# DS_ZK_FINAL.net
KiCad netlist of a schematic drawn in Altium Designer
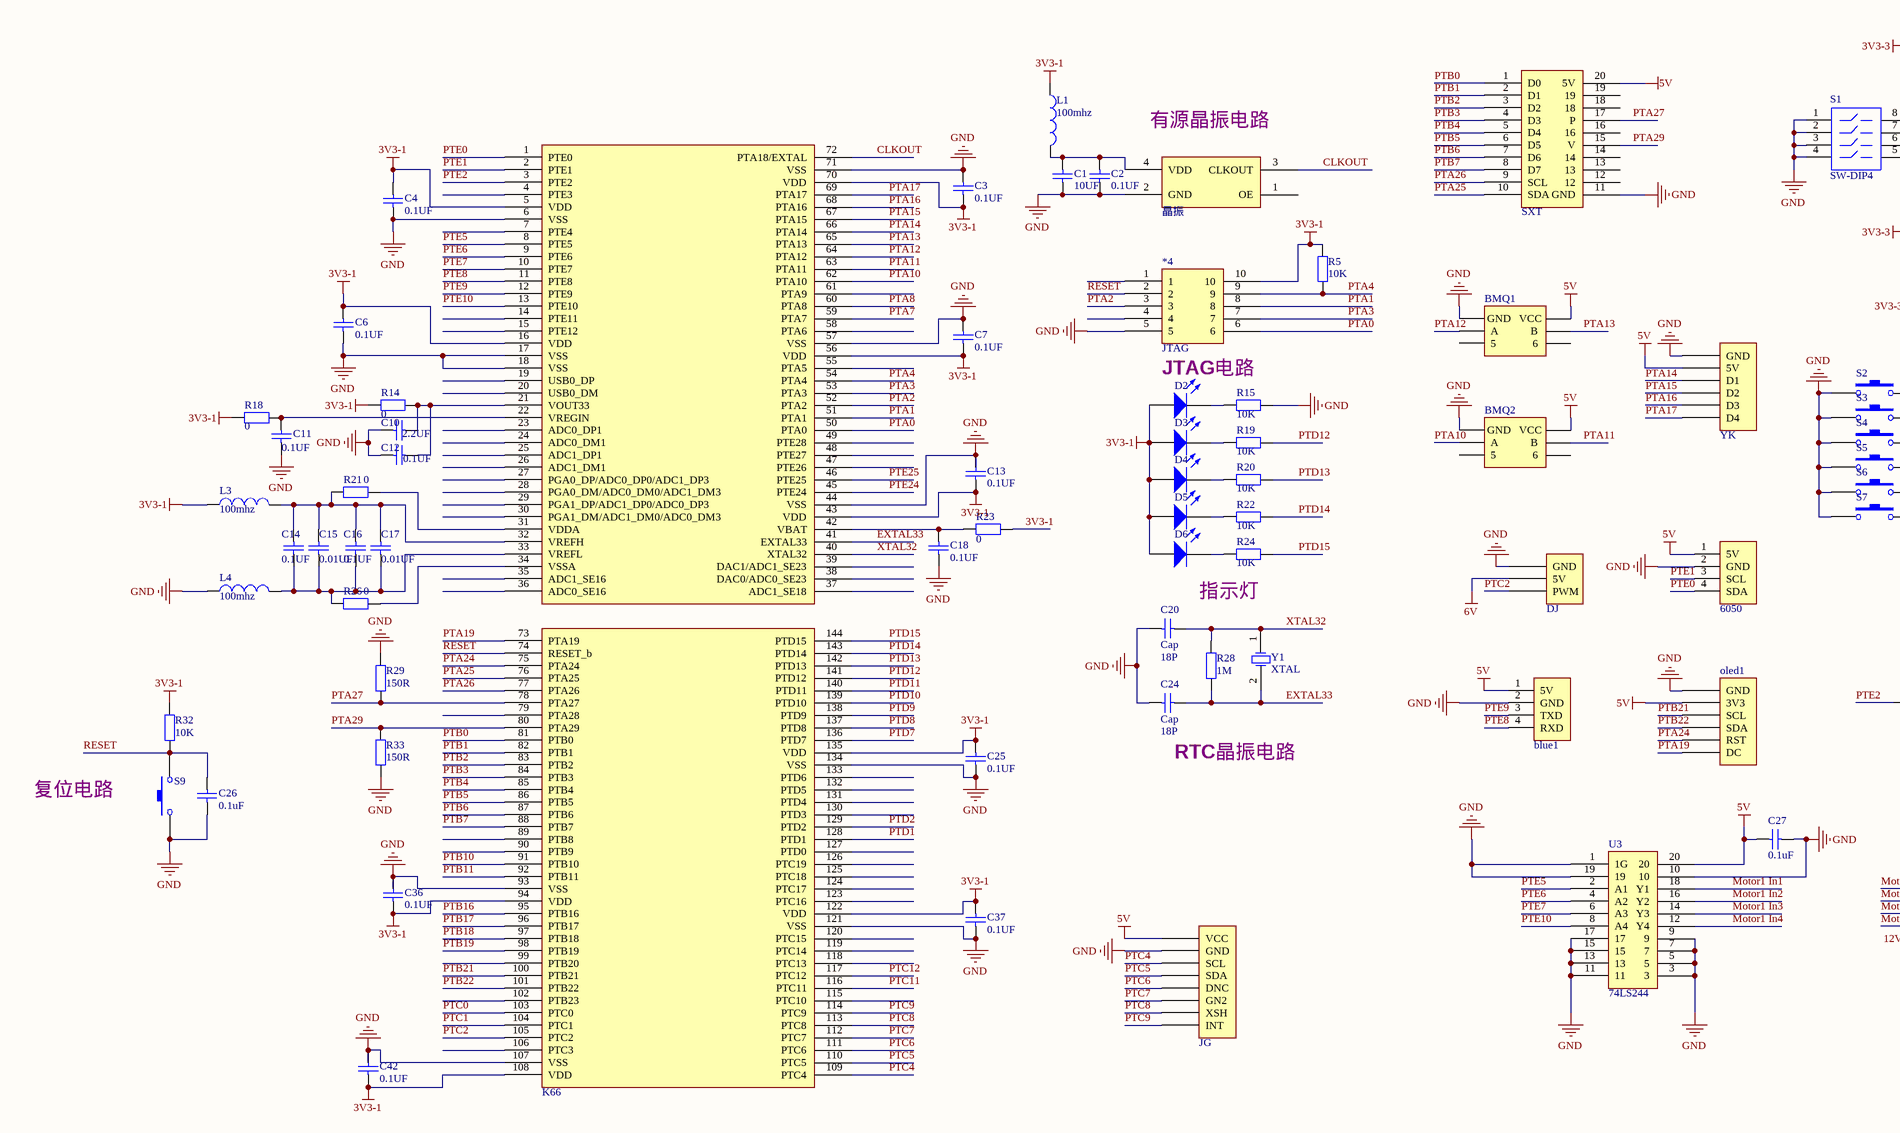
[diagram p0: DS_ZK_FINAL.SchDoc, top left]
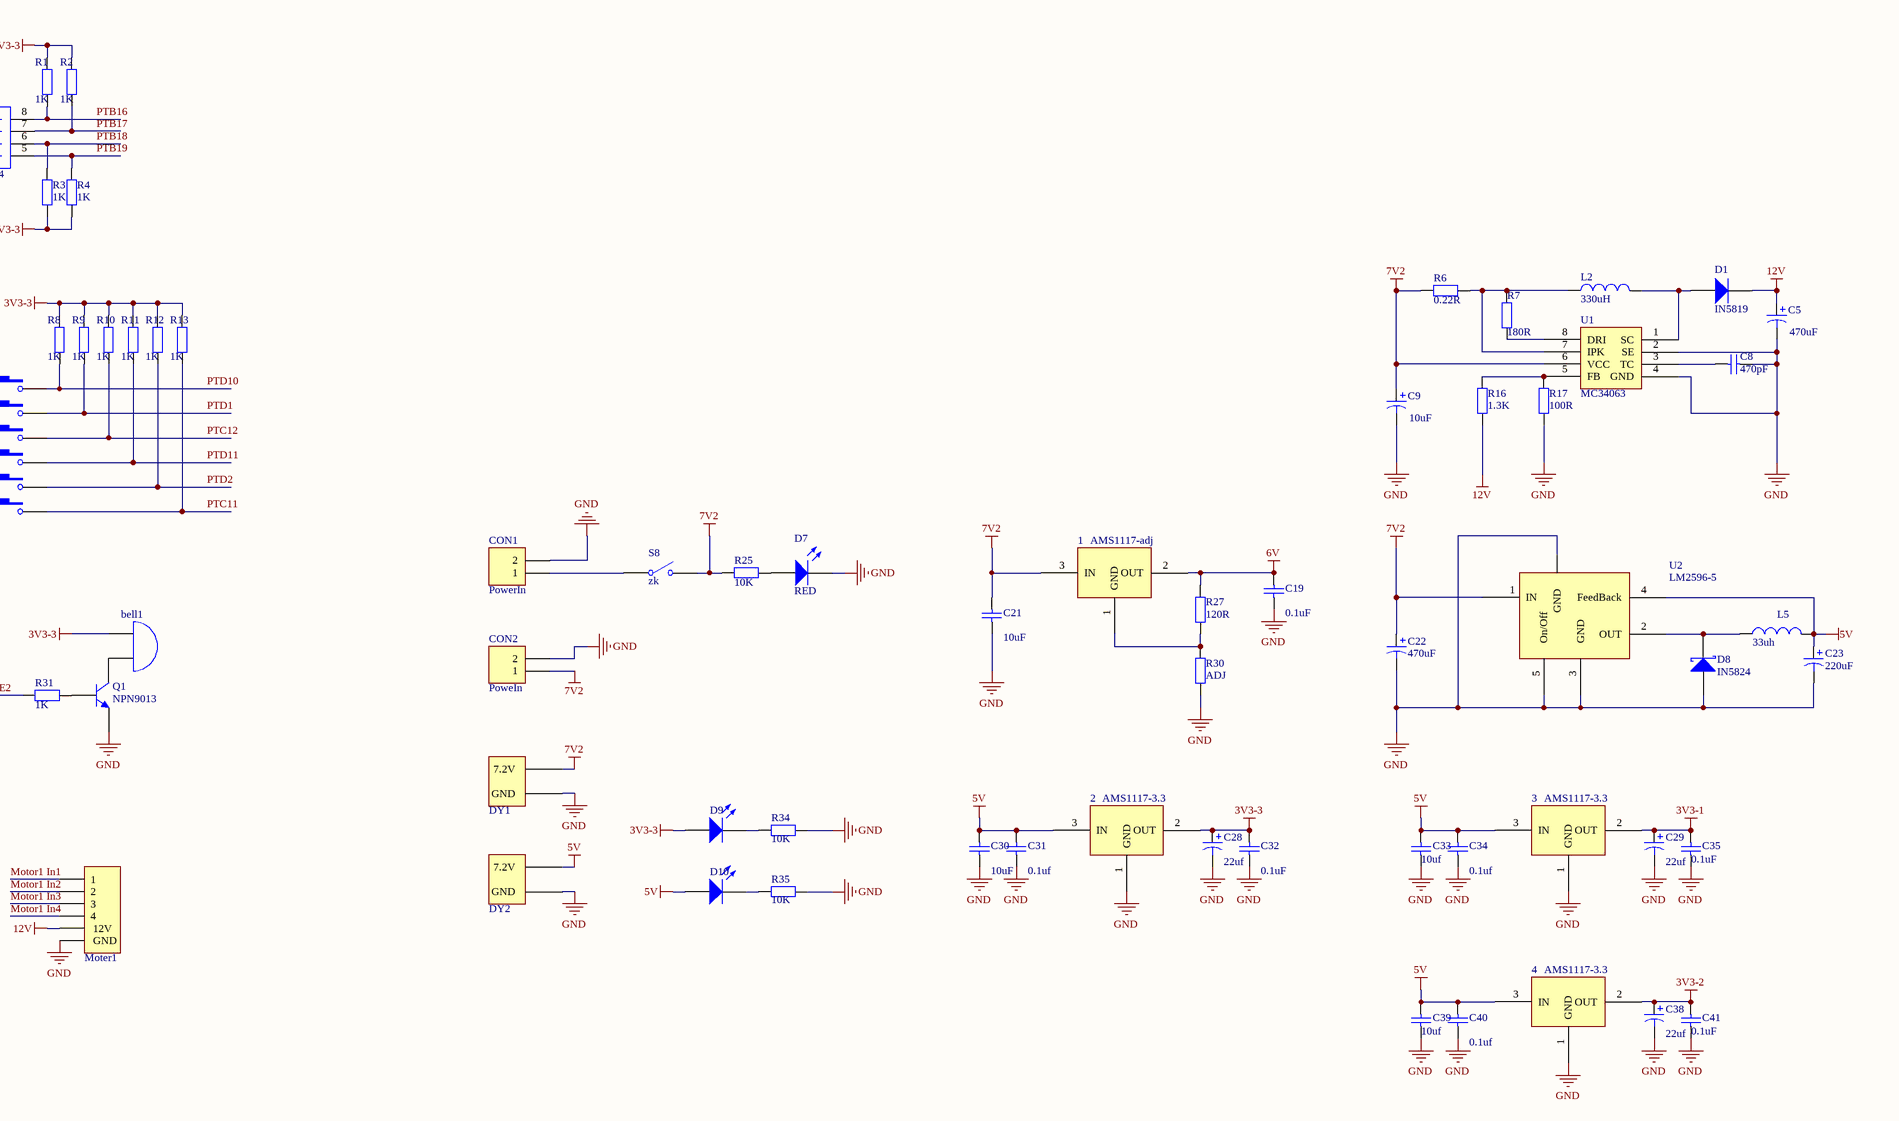
[diagram p1: DS_ZK_FINAL.SchDoc, top right]
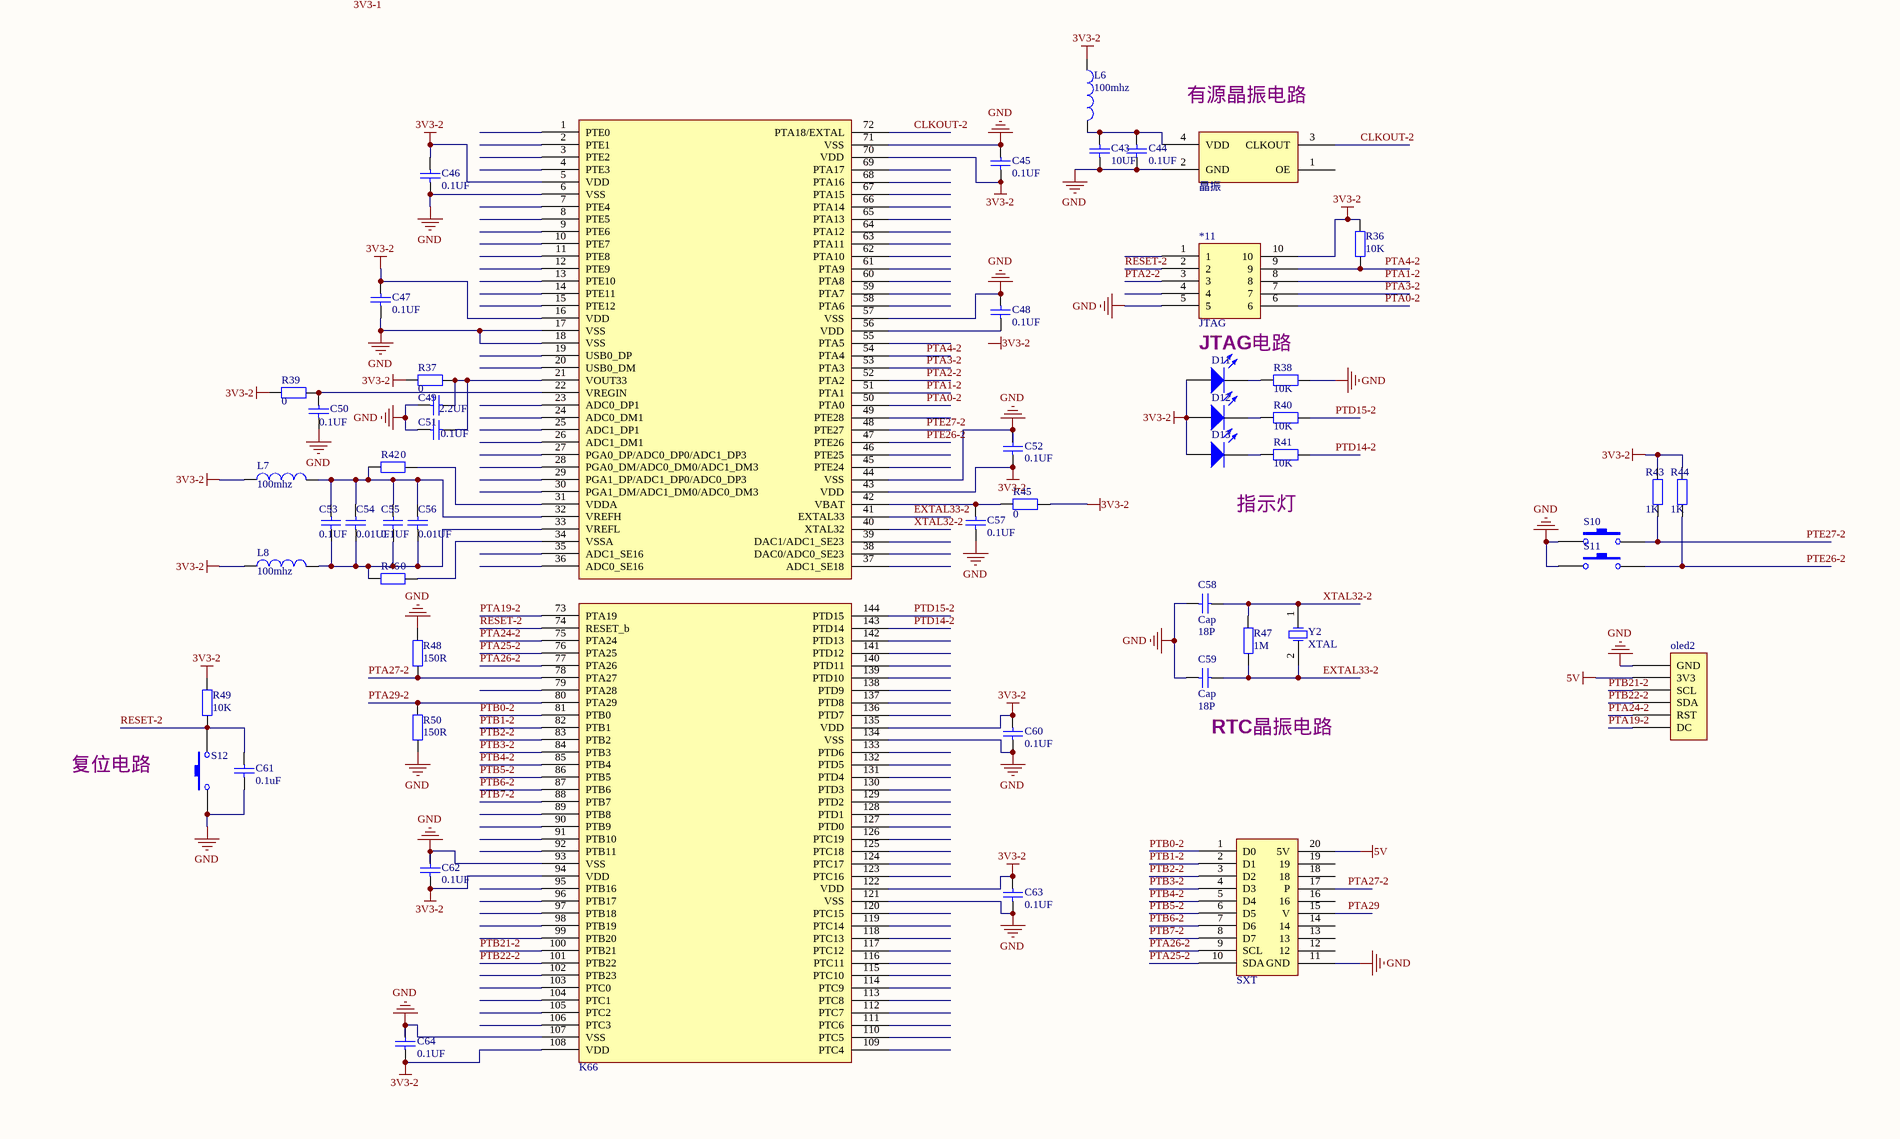
[diagram p2: DS_ZK_FINAL.SchDoc, bottom left]

(export (version "E")
  (design (tool "Eeschema 10.0.6"))
  (components
    (comp (ref "*1") (value "SXT") (footprint "SXT") (libsource (lib "DS_zk") (part "摄像头")))
    (comp (ref "*2") (value "K66") (footprint "LC-LQFP-144_20x20x05P") (libsource (lib "DS_zk") (part "K66")))
    (comp (ref "*3") (value "晶振") (footprint "LC-SMD-7050_4P") (libsource (lib "DS_zk") (part "晶振")))
    (comp (ref "*4") (value "JTAG") (footprint "HDR2X5") (libsource (lib "DS_zk") (part "JTAG")))
    (comp (ref "*5") (value "YK") (footprint "HDR1X6") (libsource (lib "DS_zk") (part "遥控")))
    (comp (ref "*6") (value "6050") (footprint "HDR1X4") (libsource (lib "DS_zk") (part "6050")))
    (comp (ref "*7") (value "DJ") (footprint "HDR1X3") (libsource (lib "DS_zk") (part "舵机")))
    (comp (ref "*8") (value "JG") (footprint "HDR1X8") (libsource (lib "DS_zk") (part "激光")))
    (comp (ref "*9") (value "K66") (footprint "LC-LQFP-144_20x20x05P") (libsource (lib "DS_zk") (part "K66")))
    (comp (ref "*10") (value "晶振") (footprint "LC-SMD-7050_4P") (libsource (lib "DS_zk") (part "晶振")))
    (comp (ref "*11") (value "JTAG") (footprint "HDR2X5") (libsource (lib "DS_zk") (part "JTAG")))
    (comp (ref "*12") (value "SXT") (footprint "SXT") (libsource (lib "DS_zk") (part "摄像头")))
    (comp (ref "1")
      (value "AMS1117-adj")
      (footprint "lm1117-5v")
      (libsource (lib "红牛板Schlib") (part "LT1117-3.3"))
    )
    (comp (ref "2")
      (value "AMS1117-3.3")
      (footprint "lm1117-5v")
      (libsource (lib "红牛板Schlib") (part "LT1117-3.3"))
    )
    (comp (ref "3")
      (value "AMS1117-3.3")
      (footprint "lm1117-5v")
      (libsource (lib "红牛板Schlib") (part "LT1117-3.3"))
    )
    (comp (ref "4")
      (value "AMS1117-3.3")
      (footprint "lm1117-5v")
      (libsource (lib "红牛板Schlib") (part "LT1117-3.3"))
    )
    (comp (ref "bell1")
      (value "Bell")
      (footprint "bezzer")
      (description "Electrical Bell")
      (fields (field (name "PUBLISHER") "Altium Limited"))
      (libsource (lib "Miscellaneous Devices") (part "Bell"))
    )
    (comp (ref "blue1")
      (value "blueteeth2")
      (footprint "HDR1X4")
      (libsource (lib "DS_zk") (part "blueteeth"))
    )
    (comp (ref "BMQ1") (value "encode_1") (footprint "HDR2X3") (libsource (lib "主控板原理图") (part "encode")))
    (comp (ref "BMQ2") (value "encode_2") (footprint "HDR2X3") (libsource (lib "主控板原理图") (part "encode")))
    (comp (ref "C1")
      (value "10UF")
      (footprint "0603")
      (description "Capacitor")
      (fields (field (name "Comment") "Cap") (field (name "PUBLISHER") "Altium Limited"))
      (libsource (lib "Miscellaneous Devices") (part "Cap"))
    )
    (comp (ref "C2")
      (value "0.1UF")
      (footprint "0603")
      (description "Capacitor")
      (fields (field (name "Comment") "Cap") (field (name "PUBLISHER") "Altium Limited"))
      (libsource (lib "Miscellaneous Devices") (part "Cap"))
    )
    (comp (ref "C3")
      (value "0.1UF")
      (footprint "0603")
      (description "Capacitor")
      (fields (field (name "Comment") "Cap") (field (name "PUBLISHER") "Altium Limited"))
      (libsource (lib "Miscellaneous Devices") (part "Cap"))
    )
    (comp (ref "C4")
      (value "0.1UF")
      (footprint "0603")
      (description "Capacitor")
      (fields (field (name "Comment") "Cap") (field (name "PUBLISHER") "Altium Limited"))
      (libsource (lib "Miscellaneous Devices") (part "Cap"))
    )
    (comp (ref "C5")
      (value "470uF")
      (footprint "470UF")
      (description "Polarized Capacitor (Surface Mount)")
      (fields (field (name "PUBLISHER") "Altium Limited"))
      (libsource (lib "Miscellaneous Devices") (part "Cap Pol3"))
    )
    (comp (ref "C6")
      (value "0.1UF")
      (footprint "0603")
      (description "Capacitor")
      (fields (field (name "Comment") "Cap") (field (name "PUBLISHER") "Altium Limited"))
      (libsource (lib "Miscellaneous Devices") (part "Cap"))
    )
    (comp (ref "C7")
      (value "0.1UF")
      (footprint "0603")
      (description "Capacitor")
      (fields (field (name "Comment") "Cap") (field (name "PUBLISHER") "Altium Limited"))
      (libsource (lib "Miscellaneous Devices") (part "Cap"))
    )
    (comp (ref "C8")
      (value "470pF")
      (footprint "0805")
      (description "Capacitor (Semiconductor SIM Model)")
      (fields (field (name "PUBLISHER") "Altium Limited"))
      (libsource (lib "Miscellaneous Devices") (part "Cap Semi"))
    )
    (comp (ref "C9")
      (value "10uF")
      (footprint "0805")
      (description "Polarized Capacitor (Surface Mount)")
      (fields (field (name "PUBLISHER") "Altium Limited"))
      (libsource (lib "Miscellaneous Devices") (part "Cap Pol3"))
    )
    (comp (ref "C10")
      (value "2.2UF")
      (footprint "0603")
      (description "Capacitor")
      (fields (field (name "Comment") "Cap") (field (name "PUBLISHER") "Altium Limited"))
      (libsource (lib "Miscellaneous Devices") (part "Cap"))
    )
    (comp (ref "C11")
      (value "0.1UF")
      (footprint "0603")
      (description "Capacitor")
      (fields (field (name "Comment") "Cap") (field (name "PUBLISHER") "Altium Limited"))
      (libsource (lib "Miscellaneous Devices") (part "Cap"))
    )
    (comp (ref "C12")
      (value "0.1UF")
      (footprint "0603")
      (description "Capacitor")
      (fields (field (name "Comment") "Cap") (field (name "PUBLISHER") "Altium Limited"))
      (libsource (lib "Miscellaneous Devices") (part "Cap"))
    )
    (comp (ref "C13")
      (value "0.1UF")
      (footprint "0603")
      (description "Capacitor")
      (fields (field (name "Comment") "Cap") (field (name "PUBLISHER") "Altium Limited"))
      (libsource (lib "Miscellaneous Devices") (part "Cap"))
    )
    (comp (ref "C14")
      (value "0.1UF")
      (footprint "0603")
      (description "Capacitor")
      (fields (field (name "Comment") "Cap") (field (name "PUBLISHER") "Altium Limited"))
      (libsource (lib "Miscellaneous Devices") (part "Cap"))
    )
    (comp (ref "C15")
      (value "0.01UF")
      (footprint "0603")
      (description "Capacitor")
      (fields (field (name "Comment") "Cap") (field (name "PUBLISHER") "Altium Limited"))
      (libsource (lib "Miscellaneous Devices") (part "Cap"))
    )
    (comp (ref "C16")
      (value "0.1UF")
      (footprint "0603")
      (description "Capacitor")
      (fields (field (name "Comment") "Cap") (field (name "PUBLISHER") "Altium Limited"))
      (libsource (lib "Miscellaneous Devices") (part "Cap"))
    )
    (comp (ref "C17")
      (value "0.01UF")
      (footprint "0603")
      (description "Capacitor")
      (fields (field (name "Comment") "Cap") (field (name "PUBLISHER") "Altium Limited"))
      (libsource (lib "Miscellaneous Devices") (part "Cap"))
    )
    (comp (ref "C18")
      (value "0.1UF")
      (footprint "0603")
      (description "Capacitor")
      (fields (field (name "Comment") "Cap") (field (name "PUBLISHER") "Altium Limited"))
      (libsource (lib "Miscellaneous Devices") (part "Cap"))
    )
    (comp (ref "C19")
      (value "0.1uF")
      (footprint "0805")
      (description "Capacitor")
      (fields (field (name "Comment") "Cap") (field (name "PUBLISHER") "Altium Limited"))
      (libsource (lib "Miscellaneous Devices") (part "Cap"))
    )
    (comp (ref "C20")
      (value "Cap")
      (footprint "0603")
      (description "Capacitor")
      (fields (field (name "ALTIUM_VALUE") "18P") (field (name "PUBLISHER") "Altium Limited"))
      (libsource (lib "Miscellaneous Devices") (part "Cap"))
    )
    (comp (ref "C21")
      (value "10uF")
      (footprint "0805")
      (description "Capacitor")
      (fields (field (name "Comment") "Cap") (field (name "PUBLISHER") "Altium Limited"))
      (libsource (lib "Miscellaneous Devices") (part "Cap"))
    )
    (comp (ref "C22")
      (value "470uF")
      (footprint "470uf")
      (description "Polarized Capacitor (Radial)")
      (fields (field (name "Comment") "Cap Pol1") (field (name "PUBLISHER") "Altium Limited"))
      (libsource (lib "主控板原理图") (part "Cap Pol1"))
    )
    (comp (ref "C23")
      (value "220uF")
      (footprint "220uf")
      (description "Polarized Capacitor (Radial)")
      (fields (field (name "Comment") "Cap Pol1") (field (name "PUBLISHER") "Altium Limited"))
      (libsource (lib "主控板原理图") (part "Cap Pol1"))
    )
    (comp (ref "C24")
      (value "Cap")
      (footprint "0603")
      (description "Capacitor")
      (fields (field (name "ALTIUM_VALUE") "18P") (field (name "PUBLISHER") "Altium Limited"))
      (libsource (lib "Miscellaneous Devices") (part "Cap"))
    )
    (comp (ref "C25")
      (value "0.1UF")
      (footprint "0603")
      (description "Capacitor")
      (fields (field (name "Comment") "Cap") (field (name "PUBLISHER") "Altium Limited"))
      (libsource (lib "Miscellaneous Devices") (part "Cap"))
    )
    (comp (ref "C26")
      (value "0.1uF")
      (footprint "0805")
      (description "Capacitor")
      (fields (field (name "Comment") "Cap") (field (name "PUBLISHER") "Altium Limited"))
      (libsource (lib "霍振飞") (part "Cap"))
    )
    (comp (ref "C27")
      (value "0.1uF")
      (footprint "0805")
      (description "Capacitor (Semiconductor SIM Model)")
      (fields (field (name "PUBLISHER") "Altium Limited"))
      (libsource (lib "Miscellaneous Devices") (part "Cap Semi"))
    )
    (comp (ref "C28")
      (value "22uf")
      (footprint "0805")
      (description "Polarized Capacitor (Radial)")
      (fields (field (name "Comment") "Cap Pol1") (field (name "PUBLISHER") "Altium Limited"))
      (libsource (lib "Miscellaneous Devices") (part "Cap Pol1"))
    )
    (comp (ref "C29")
      (value "22uf")
      (footprint "0805")
      (description "Polarized Capacitor (Radial)")
      (fields (field (name "Comment") "Cap Pol1") (field (name "PUBLISHER") "Altium Limited"))
      (libsource (lib "Miscellaneous Devices") (part "Cap Pol1"))
    )
    (comp (ref "C30")
      (value "10uF")
      (footprint "0805")
      (description "Capacitor")
      (fields (field (name "Comment") "Cap") (field (name "PUBLISHER") "Altium Limited"))
      (libsource (lib "Miscellaneous Devices") (part "Cap"))
    )
    (comp (ref "C31")
      (value "0.1uf")
      (footprint "0805")
      (description "Capacitor")
      (fields (field (name "Comment") "Cap") (field (name "PUBLISHER") "Altium Limited"))
      (libsource (lib "Miscellaneous Devices") (part "Cap"))
    )
    (comp (ref "C32")
      (value "0.1uF")
      (footprint "0805")
      (description "Capacitor")
      (fields (field (name "Comment") "Cap") (field (name "PUBLISHER") "Altium Limited"))
      (libsource (lib "Miscellaneous Devices") (part "Cap"))
    )
    (comp (ref "C33")
      (value "10uf")
      (footprint "0805")
      (description "Capacitor")
      (fields (field (name "Comment") "Cap") (field (name "PUBLISHER") "Altium Limited"))
      (libsource (lib "Miscellaneous Devices") (part "Cap"))
    )
    (comp (ref "C34")
      (value "0.1uf")
      (footprint "0805")
      (description "Capacitor")
      (fields (field (name "Comment") "Cap") (field (name "PUBLISHER") "Altium Limited"))
      (libsource (lib "Miscellaneous Devices") (part "Cap"))
    )
    (comp (ref "C35")
      (value "0.1uF")
      (footprint "0805")
      (description "Capacitor")
      (fields (field (name "Comment") "Cap") (field (name "PUBLISHER") "Altium Limited"))
      (libsource (lib "Miscellaneous Devices") (part "Cap"))
    )
    (comp (ref "C36")
      (value "0.1UF")
      (footprint "0603")
      (description "Capacitor")
      (fields (field (name "Comment") "Cap") (field (name "PUBLISHER") "Altium Limited"))
      (libsource (lib "Miscellaneous Devices") (part "Cap"))
    )
    (comp (ref "C37")
      (value "0.1UF")
      (footprint "0603")
      (description "Capacitor")
      (fields (field (name "Comment") "Cap") (field (name "PUBLISHER") "Altium Limited"))
      (libsource (lib "Miscellaneous Devices") (part "Cap"))
    )
    (comp (ref "C38")
      (value "22uf")
      (footprint "0805")
      (description "Polarized Capacitor (Radial)")
      (fields (field (name "Comment") "Cap Pol1") (field (name "PUBLISHER") "Altium Limited"))
      (libsource (lib "Miscellaneous Devices") (part "Cap Pol1"))
    )
    (comp (ref "C39")
      (value "10uf")
      (footprint "0805")
      (description "Capacitor")
      (fields (field (name "Comment") "Cap") (field (name "PUBLISHER") "Altium Limited"))
      (libsource (lib "Miscellaneous Devices") (part "Cap"))
    )
    (comp (ref "C40")
      (value "0.1uf")
      (footprint "0805")
      (description "Capacitor")
      (fields (field (name "Comment") "Cap") (field (name "PUBLISHER") "Altium Limited"))
      (libsource (lib "Miscellaneous Devices") (part "Cap"))
    )
    (comp (ref "C41")
      (value "0.1uF")
      (footprint "0805")
      (description "Capacitor")
      (fields (field (name "Comment") "Cap") (field (name "PUBLISHER") "Altium Limited"))
      (libsource (lib "Miscellaneous Devices") (part "Cap"))
    )
    (comp (ref "C42")
      (value "0.1UF")
      (footprint "0603")
      (description "Capacitor")
      (fields (field (name "Comment") "Cap") (field (name "PUBLISHER") "Altium Limited"))
      (libsource (lib "Miscellaneous Devices") (part "Cap"))
    )
    (comp (ref "C43")
      (value "10UF")
      (footprint "0603")
      (description "Capacitor")
      (fields (field (name "Comment") "Cap") (field (name "PUBLISHER") "Altium Limited"))
      (libsource (lib "Miscellaneous Devices") (part "Cap"))
    )
    (comp (ref "C44")
      (value "0.1UF")
      (footprint "0603")
      (description "Capacitor")
      (fields (field (name "Comment") "Cap") (field (name "PUBLISHER") "Altium Limited"))
      (libsource (lib "Miscellaneous Devices") (part "Cap"))
    )
    (comp (ref "C45")
      (value "0.1UF")
      (footprint "0603")
      (description "Capacitor")
      (fields (field (name "Comment") "Cap") (field (name "PUBLISHER") "Altium Limited"))
      (libsource (lib "Miscellaneous Devices") (part "Cap"))
    )
    (comp (ref "C46")
      (value "0.1UF")
      (footprint "0603")
      (description "Capacitor")
      (fields (field (name "Comment") "Cap") (field (name "PUBLISHER") "Altium Limited"))
      (libsource (lib "Miscellaneous Devices") (part "Cap"))
    )
    (comp (ref "C47")
      (value "0.1UF")
      (footprint "0603")
      (description "Capacitor")
      (fields (field (name "Comment") "Cap") (field (name "PUBLISHER") "Altium Limited"))
      (libsource (lib "Miscellaneous Devices") (part "Cap"))
    )
    (comp (ref "C48")
      (value "0.1UF")
      (footprint "0603")
      (description "Capacitor")
      (fields (field (name "Comment") "Cap") (field (name "PUBLISHER") "Altium Limited"))
      (libsource (lib "Miscellaneous Devices") (part "Cap"))
    )
    (comp (ref "C49")
      (value "2.2UF")
      (footprint "0603")
      (description "Capacitor")
      (fields (field (name "Comment") "Cap") (field (name "PUBLISHER") "Altium Limited"))
      (libsource (lib "Miscellaneous Devices") (part "Cap"))
    )
    (comp (ref "C50")
      (value "0.1UF")
      (footprint "0603")
      (description "Capacitor")
      (fields (field (name "Comment") "Cap") (field (name "PUBLISHER") "Altium Limited"))
      (libsource (lib "Miscellaneous Devices") (part "Cap"))
    )
    (comp (ref "C51")
      (value "0.1UF")
      (footprint "0603")
      (description "Capacitor")
      (fields (field (name "Comment") "Cap") (field (name "PUBLISHER") "Altium Limited"))
      (libsource (lib "Miscellaneous Devices") (part "Cap"))
    )
    (comp (ref "C52")
      (value "0.1UF")
      (footprint "0603")
      (description "Capacitor")
      (fields (field (name "Comment") "Cap") (field (name "PUBLISHER") "Altium Limited"))
      (libsource (lib "Miscellaneous Devices") (part "Cap"))
    )
    (comp (ref "C53")
      (value "0.1UF")
      (footprint "0603")
      (description "Capacitor")
      (fields (field (name "Comment") "Cap") (field (name "PUBLISHER") "Altium Limited"))
      (libsource (lib "Miscellaneous Devices") (part "Cap"))
    )
    (comp (ref "C54")
      (value "0.01UF")
      (footprint "0603")
      (description "Capacitor")
      (fields (field (name "Comment") "Cap") (field (name "PUBLISHER") "Altium Limited"))
      (libsource (lib "Miscellaneous Devices") (part "Cap"))
    )
    (comp (ref "C55")
      (value "0.1UF")
      (footprint "0603")
      (description "Capacitor")
      (fields (field (name "Comment") "Cap") (field (name "PUBLISHER") "Altium Limited"))
      (libsource (lib "Miscellaneous Devices") (part "Cap"))
    )
    (comp (ref "C56")
      (value "0.01UF")
      (footprint "0603")
      (description "Capacitor")
      (fields (field (name "Comment") "Cap") (field (name "PUBLISHER") "Altium Limited"))
      (libsource (lib "Miscellaneous Devices") (part "Cap"))
    )
    (comp (ref "C57")
      (value "0.1UF")
      (footprint "0603")
      (description "Capacitor")
      (fields (field (name "Comment") "Cap") (field (name "PUBLISHER") "Altium Limited"))
      (libsource (lib "Miscellaneous Devices") (part "Cap"))
    )
    (comp (ref "C58")
      (value "Cap")
      (footprint "0603")
      (description "Capacitor")
      (fields (field (name "ALTIUM_VALUE") "18P") (field (name "PUBLISHER") "Altium Limited"))
      (libsource (lib "Miscellaneous Devices") (part "Cap"))
    )
    (comp (ref "C59")
      (value "Cap")
      (footprint "0603")
      (description "Capacitor")
      (fields (field (name "ALTIUM_VALUE") "18P") (field (name "PUBLISHER") "Altium Limited"))
      (libsource (lib "Miscellaneous Devices") (part "Cap"))
    )
    (comp (ref "C60")
      (value "0.1UF")
      (footprint "0603")
      (description "Capacitor")
      (fields (field (name "Comment") "Cap") (field (name "PUBLISHER") "Altium Limited"))
      (libsource (lib "Miscellaneous Devices") (part "Cap"))
    )
    (comp (ref "C61")
      (value "0.1uF")
      (footprint "0805")
      (description "Capacitor")
      (fields (field (name "Comment") "Cap") (field (name "PUBLISHER") "Altium Limited"))
      (libsource (lib "霍振飞") (part "Cap"))
    )
    (comp (ref "C62")
      (value "0.1UF")
      (footprint "0603")
      (description "Capacitor")
      (fields (field (name "Comment") "Cap") (field (name "PUBLISHER") "Altium Limited"))
      (libsource (lib "Miscellaneous Devices") (part "Cap"))
    )
    (comp (ref "C63")
      (value "0.1UF")
      (footprint "0603")
      (description "Capacitor")
      (fields (field (name "Comment") "Cap") (field (name "PUBLISHER") "Altium Limited"))
      (libsource (lib "Miscellaneous Devices") (part "Cap"))
    )
    (comp (ref "C64")
      (value "0.1UF")
      (footprint "0603")
      (description "Capacitor")
      (fields (field (name "Comment") "Cap") (field (name "PUBLISHER") "Altium Limited"))
      (libsource (lib "Miscellaneous Devices") (part "Cap"))
    )
    (comp (ref "CON1")
      (value "PowerIn")
      (footprint "DIZUO")
      (description "Header, 2-Pin")
      (fields (field (name "PUBLISHER") "Altium Limited"))
      (libsource (lib "Miscellaneous Connectors") (part "Header 2"))
    )
    (comp (ref "CON2")
      (value "PoweIn")
      (footprint "KF301-2P")
      (description "Header, 2-Pin")
      (fields (field (name "PUBLISHER") "Altium Limited"))
      (libsource (lib "Miscellaneous Connectors") (part "Header 2"))
    )
    (comp (ref "D1")
      (value "IN5819")
      (footprint "0805LED")
      (description "Default Diode")
      (fields (field (name "PUBLISHER") "Altium Limited"))
      (libsource (lib "Miscellaneous Devices") (part "Diode"))
    )
    (comp (ref "D2")
      (value "LED0")
      (footprint "0805LED")
      (description "Typical INFRARED GaAs LED")
      (fields (field (name "PUBLISHER") "Altium Limited"))
      (libsource (lib "Miscellaneous Devices") (part "LED0"))
    )
    (comp (ref "D3")
      (value "LED0")
      (footprint "0805LED")
      (description "Typical INFRARED GaAs LED")
      (fields (field (name "PUBLISHER") "Altium Limited"))
      (libsource (lib "Miscellaneous Devices") (part "LED0"))
    )
    (comp (ref "D4")
      (value "LED0")
      (footprint "0805LED")
      (description "Typical INFRARED GaAs LED")
      (fields (field (name "PUBLISHER") "Altium Limited"))
      (libsource (lib "Miscellaneous Devices") (part "LED0"))
    )
    (comp (ref "D5")
      (value "LED0")
      (footprint "0805LED")
      (description "Typical INFRARED GaAs LED")
      (fields (field (name "PUBLISHER") "Altium Limited"))
      (libsource (lib "Miscellaneous Devices") (part "LED0"))
    )
    (comp (ref "D6")
      (value "LED0")
      (footprint "0805LED")
      (description "Typical INFRARED GaAs LED")
      (fields (field (name "PUBLISHER") "Altium Limited"))
      (libsource (lib "Miscellaneous Devices") (part "LED0"))
    )
    (comp (ref "D7")
      (value "RED")
      (footprint "0805LED")
      (description "Typical RED, GREEN, YELLOW, AMBER GaAs LED")
      (fields (field (name "PUBLISHER") "Altium Limited"))
      (libsource (lib "主控板原理图") (part "LED2"))
    )
    (comp (ref "D8") (value "IN5824") (footprint "1N5824") (libsource (lib "主控板原理图") (part "IN5824")))
    (comp (ref "D9")
      (value "LED0")
      (footprint "0805LED")
      (description "Typical INFRARED GaAs LED")
      (fields (field (name "PUBLISHER") "Altium Limited"))
      (libsource (lib "Miscellaneous Devices") (part "LED0"))
    )
    (comp (ref "D10")
      (value "LED0")
      (footprint "0805LED")
      (description "Typical INFRARED GaAs LED")
      (fields (field (name "PUBLISHER") "Altium Limited"))
      (libsource (lib "Miscellaneous Devices") (part "LED0"))
    )
    (comp (ref "D11")
      (value "LED0")
      (footprint "0805LED")
      (description "Typical INFRARED GaAs LED")
      (fields (field (name "PUBLISHER") "Altium Limited"))
      (libsource (lib "Miscellaneous Devices") (part "LED0"))
    )
    (comp (ref "D12")
      (value "LED0")
      (footprint "0805LED")
      (description "Typical INFRARED GaAs LED")
      (fields (field (name "PUBLISHER") "Altium Limited"))
      (libsource (lib "Miscellaneous Devices") (part "LED0"))
    )
    (comp (ref "D13")
      (value "LED0")
      (footprint "0805LED")
      (description "Typical INFRARED GaAs LED")
      (fields (field (name "PUBLISHER") "Altium Limited"))
      (libsource (lib "Miscellaneous Devices") (part "LED0"))
    )
    (comp (ref "DY1") (value "H1") (footprint "HDR1X2") (libsource (lib "DS_zk") (part "H1")))
    (comp (ref "DY2") (value "H1") (footprint "HDR1X2") (libsource (lib "DS_zk") (part "H1")))
    (comp (ref "L1")
      (value "100mhz")
      (footprint "0603")
      (description "Inductor")
      (fields (field (name "PUBLISHER") "Altium Limited"))
      (libsource (lib "Miscellaneous Devices") (part "Inductor"))
    )
    (comp (ref "L2")
      (value "330uH")
      (footprint "diangan")
      (description "Inductor")
      (fields (field (name "PUBLISHER") "Altium Limited"))
      (libsource (lib "Miscellaneous Devices") (part "Inductor"))
    )
    (comp (ref "L3")
      (value "100mhz")
      (footprint "0603")
      (description "Inductor")
      (fields (field (name "PUBLISHER") "Altium Limited"))
      (libsource (lib "Miscellaneous Devices") (part "Inductor"))
    )
    (comp (ref "L4")
      (value "100mhz")
      (footprint "0603")
      (description "Inductor")
      (fields (field (name "PUBLISHER") "Altium Limited"))
      (libsource (lib "Miscellaneous Devices") (part "Inductor"))
    )
    (comp (ref "L5")
      (value "33uh")
      (footprint "diangan")
      (description "Inductor")
      (fields (field (name "PUBLISHER") "Altium Limited"))
      (libsource (lib "主控板原理图") (part "Inductor"))
    )
    (comp (ref "L6")
      (value "100mhz")
      (footprint "0603")
      (description "Inductor")
      (fields (field (name "PUBLISHER") "Altium Limited"))
      (libsource (lib "Miscellaneous Devices") (part "Inductor"))
    )
    (comp (ref "L7")
      (value "100mhz")
      (footprint "0603")
      (description "Inductor")
      (fields (field (name "PUBLISHER") "Altium Limited"))
      (libsource (lib "Miscellaneous Devices") (part "Inductor"))
    )
    (comp (ref "L8")
      (value "100mhz")
      (footprint "0603")
      (description "Inductor")
      (fields (field (name "PUBLISHER") "Altium Limited"))
      (libsource (lib "Miscellaneous Devices") (part "Inductor"))
    )
    (comp (ref "Moter1") (value "Motor") (footprint "HDR1X6") (libsource (lib "DS_zk") (part "Motor")))
    (comp (ref "oled1") (value "OLED") (footprint "HDR1X6") (libsource (lib "LY") (part "OLED")))
    (comp (ref "oled2") (value "OLED") (footprint "HDR1X6") (libsource (lib "LY") (part "OLED")))
    (comp (ref "Q1")
      (value "NPN9013")
      (footprint "npn9013")
      (description "NPN General Purpose Amplifier")
      (fields (field (name "PUBLISHER") "Altium Limited"))
      (libsource (lib "Miscellaneous Devices") (part "2N3904"))
    )
    (comp (ref "R1")
      (value "1K")
      (footprint "0805")
      (description "Resistor")
      (fields (field (name "Comment") "Res2") (field (name "PUBLISHER") "Altium Limited"))
      (libsource (lib "主控板原理图") (part "Res2"))
    )
    (comp (ref "R2")
      (value "1K")
      (footprint "0805")
      (description "Resistor")
      (fields (field (name "Comment") "Res2") (field (name "PUBLISHER") "Altium Limited"))
      (libsource (lib "主控板原理图") (part "Res2"))
    )
    (comp (ref "R3")
      (value "1K")
      (footprint "0805")
      (description "Resistor")
      (fields (field (name "Comment") "Res2") (field (name "PUBLISHER") "Altium Limited"))
      (libsource (lib "") (part "Res2_2"))
    )
    (comp (ref "R4")
      (value "1K")
      (footprint "0805")
      (description "Resistor")
      (fields (field (name "Comment") "Res2") (field (name "PUBLISHER") "Altium Limited"))
      (libsource (lib "主控板原理图") (part "Res2"))
    )
    (comp (ref "R5")
      (value "10K")
      (footprint "0805")
      (description "Resistor")
      (fields (field (name "Comment") "Res2") (field (name "PUBLISHER") "Altium Limited"))
      (libsource (lib "Miscellaneous Devices") (part "Res2"))
    )
    (comp (ref "R6")
      (value "0.22R")
      (footprint "0603")
      (description "Resistor")
      (fields (field (name "PUBLISHER") "Altium Limited"))
      (libsource (lib "") (part "Res2_2"))
    )
    (comp (ref "R7")
      (value "180R")
      (footprint "0603")
      (description "Resistor")
      (fields (field (name "PUBLISHER") "Altium Limited"))
      (libsource (lib "Miscellaneous Devices") (part "Res2"))
    )
    (comp (ref "R8")
      (value "1K")
      (footprint "0805")
      (description "Resistor")
      (fields (field (name "Comment") "Res2") (field (name "PUBLISHER") "Altium Limited"))
      (libsource (lib "主控板原理图") (part "Res2"))
    )
    (comp (ref "R9")
      (value "1K")
      (footprint "0805")
      (description "Resistor")
      (fields (field (name "Comment") "Res2") (field (name "PUBLISHER") "Altium Limited"))
      (libsource (lib "主控板原理图") (part "Res2"))
    )
    (comp (ref "R10")
      (value "1K")
      (footprint "0805")
      (description "Resistor")
      (fields (field (name "Comment") "Res2") (field (name "PUBLISHER") "Altium Limited"))
      (libsource (lib "主控板原理图") (part "Res2"))
    )
    (comp (ref "R11")
      (value "1K")
      (footprint "0805")
      (description "Resistor")
      (fields (field (name "Comment") "Res2") (field (name "PUBLISHER") "Altium Limited"))
      (libsource (lib "主控板原理图") (part "Res2"))
    )
    (comp (ref "R12")
      (value "1K")
      (footprint "0805")
      (description "Resistor")
      (fields (field (name "Comment") "Res2") (field (name "PUBLISHER") "Altium Limited"))
      (libsource (lib "主控板原理图") (part "Res2"))
    )
    (comp (ref "R13")
      (value "1K")
      (footprint "0805")
      (description "Resistor")
      (fields (field (name "Comment") "Res2") (field (name "PUBLISHER") "Altium Limited"))
      (libsource (lib "主控板原理图") (part "Res2"))
    )
    (comp (ref "R14")
      (value "0")
      (footprint "0603")
      (description "Resistor")
      (fields (field (name "Comment") "Res2") (field (name "PUBLISHER") "Altium Limited"))
      (libsource (lib "") (part "Res2_1"))
    )
    (comp (ref "R15")
      (value "10K")
      (footprint "0805")
      (description "Resistor")
      (fields (field (name "Comment") "Res2") (field (name "PUBLISHER") "Altium Limited"))
      (libsource (lib "") (part "Res2_1"))
    )
    (comp (ref "R16")
      (value "1.3K")
      (footprint "0603")
      (description "Resistor")
      (fields (field (name "PUBLISHER") "Altium Limited"))
      (libsource (lib "") (part "Res2_3"))
    )
    (comp (ref "R17")
      (value "100R")
      (footprint "0603")
      (description "Resistor")
      (fields (field (name "PUBLISHER") "Altium Limited"))
      (libsource (lib "") (part "Res2_3"))
    )
    (comp (ref "R18")
      (value "0")
      (footprint "0603")
      (description "Resistor")
      (fields (field (name "Comment") "Res2") (field (name "PUBLISHER") "Altium Limited"))
      (libsource (lib "") (part "Res2_1"))
    )
    (comp (ref "R19")
      (value "10K")
      (footprint "0805")
      (description "Resistor")
      (fields (field (name "Comment") "Res2") (field (name "PUBLISHER") "Altium Limited"))
      (libsource (lib "") (part "Res2_1"))
    )
    (comp (ref "R20")
      (value "10K")
      (footprint "0805")
      (description "Resistor")
      (fields (field (name "Comment") "Res2") (field (name "PUBLISHER") "Altium Limited"))
      (libsource (lib "") (part "Res2_1"))
    )
    (comp (ref "R21")
      (value "0")
      (footprint "0603")
      (description "Resistor")
      (fields (field (name "Comment") "Res2") (field (name "PUBLISHER") "Altium Limited"))
      (libsource (lib "") (part "Res2_1"))
    )
    (comp (ref "R22")
      (value "10K")
      (footprint "0805")
      (description "Resistor")
      (fields (field (name "Comment") "Res2") (field (name "PUBLISHER") "Altium Limited"))
      (libsource (lib "") (part "Res2_1"))
    )
    (comp (ref "R23")
      (value "0")
      (footprint "0603")
      (description "Resistor")
      (fields (field (name "Comment") "Res2") (field (name "PUBLISHER") "Altium Limited"))
      (libsource (lib "") (part "Res2_2"))
    )
    (comp (ref "R24")
      (value "10K")
      (footprint "0805")
      (description "Resistor")
      (fields (field (name "Comment") "Res2") (field (name "PUBLISHER") "Altium Limited"))
      (libsource (lib "") (part "Res2_1"))
    )
    (comp (ref "R25")
      (value "10K")
      (footprint "0805")
      (description "Resistor")
      (fields (field (name "Comment") "Res2") (field (name "PUBLISHER") "Altium Limited"))
      (libsource (lib "") (part "Res2_1"))
    )
    (comp (ref "R26")
      (value "0")
      (footprint "0603")
      (description "Resistor")
      (fields (field (name "Comment") "Res2") (field (name "PUBLISHER") "Altium Limited"))
      (libsource (lib "") (part "Res2_1"))
    )
    (comp (ref "R27")
      (value "120R")
      (footprint "0805")
      (description "Resistor")
      (fields (field (name "Comment") "Res2") (field (name "PUBLISHER") "Altium Limited"))
      (libsource (lib "Miscellaneous Devices") (part "Res2"))
    )
    (comp (ref "R28")
      (value "1M")
      (footprint "0603")
      (description "Resistor")
      (fields (field (name "Comment") "Res2") (field (name "PUBLISHER") "Altium Limited"))
      (libsource (lib "Miscellaneous Devices") (part "Res2"))
    )
    (comp (ref "R29")
      (value "150R")
      (footprint "0805")
      (description "Resistor")
      (fields (field (name "Comment") "Res2") (field (name "PUBLISHER") "Altium Limited"))
      (libsource (lib "Miscellaneous Devices") (part "Res2"))
    )
    (comp (ref "R30")
      (value "ADJ")
      (footprint "1*2")
      (description "Resistor")
      (fields (field (name "Comment") "Res2") (field (name "PUBLISHER") "Altium Limited"))
      (libsource (lib "Miscellaneous Devices") (part "Res2"))
    )
    (comp (ref "R31")
      (value "1K")
      (footprint "0805")
      (description "Resistor")
      (fields (field (name "Comment") "Res2") (field (name "PUBLISHER") "Altium Limited"))
      (libsource (lib "") (part "Res2_3"))
    )
    (comp (ref "R32")
      (value "10K")
      (footprint "0805")
      (description "Resistor")
      (fields (field (name "Comment") "Res2") (field (name "PUBLISHER") "Altium Limited"))
      (libsource (lib "霍振飞") (part "Res2"))
    )
    (comp (ref "R33")
      (value "150R")
      (footprint "0805")
      (description "Resistor")
      (fields (field (name "Comment") "Res2") (field (name "PUBLISHER") "Altium Limited"))
      (libsource (lib "Miscellaneous Devices") (part "Res2"))
    )
    (comp (ref "R34")
      (value "10K")
      (footprint "0805")
      (description "Resistor")
      (fields (field (name "Comment") "Res2") (field (name "PUBLISHER") "Altium Limited"))
      (libsource (lib "") (part "Res2_1"))
    )
    (comp (ref "R35")
      (value "10K")
      (footprint "0805")
      (description "Resistor")
      (fields (field (name "Comment") "Res2") (field (name "PUBLISHER") "Altium Limited"))
      (libsource (lib "") (part "Res2_1"))
    )
    (comp (ref "R36")
      (value "10K")
      (footprint "0805")
      (description "Resistor")
      (fields (field (name "Comment") "Res2") (field (name "PUBLISHER") "Altium Limited"))
      (libsource (lib "Miscellaneous Devices") (part "Res2"))
    )
    (comp (ref "R37")
      (value "0")
      (footprint "0603")
      (description "Resistor")
      (fields (field (name "Comment") "Res2") (field (name "PUBLISHER") "Altium Limited"))
      (libsource (lib "") (part "Res2_1"))
    )
    (comp (ref "R38")
      (value "10K")
      (footprint "0805")
      (description "Resistor")
      (fields (field (name "Comment") "Res2") (field (name "PUBLISHER") "Altium Limited"))
      (libsource (lib "") (part "Res2_1"))
    )
    (comp (ref "R39")
      (value "0")
      (footprint "0603")
      (description "Resistor")
      (fields (field (name "Comment") "Res2") (field (name "PUBLISHER") "Altium Limited"))
      (libsource (lib "") (part "Res2_1"))
    )
    (comp (ref "R40")
      (value "10K")
      (footprint "0805")
      (description "Resistor")
      (fields (field (name "Comment") "Res2") (field (name "PUBLISHER") "Altium Limited"))
      (libsource (lib "") (part "Res2_1"))
    )
    (comp (ref "R41")
      (value "10K")
      (footprint "0805")
      (description "Resistor")
      (fields (field (name "Comment") "Res2") (field (name "PUBLISHER") "Altium Limited"))
      (libsource (lib "") (part "Res2_1"))
    )
    (comp (ref "R42")
      (value "0")
      (footprint "0603")
      (description "Resistor")
      (fields (field (name "Comment") "Res2") (field (name "PUBLISHER") "Altium Limited"))
      (libsource (lib "") (part "Res2_1"))
    )
    (comp (ref "R43")
      (value "1K")
      (footprint "0805")
      (description "Resistor")
      (fields (field (name "Comment") "Res2") (field (name "PUBLISHER") "Altium Limited"))
      (libsource (lib "主控板原理图") (part "Res2"))
    )
    (comp (ref "R44")
      (value "1K")
      (footprint "0805")
      (description "Resistor")
      (fields (field (name "Comment") "Res2") (field (name "PUBLISHER") "Altium Limited"))
      (libsource (lib "主控板原理图") (part "Res2"))
    )
    (comp (ref "R45")
      (value "0")
      (footprint "0603")
      (description "Resistor")
      (fields (field (name "Comment") "Res2") (field (name "PUBLISHER") "Altium Limited"))
      (libsource (lib "") (part "Res2_2"))
    )
    (comp (ref "R46")
      (value "0")
      (footprint "0603")
      (description "Resistor")
      (fields (field (name "Comment") "Res2") (field (name "PUBLISHER") "Altium Limited"))
      (libsource (lib "") (part "Res2_1"))
    )
    (comp (ref "R47")
      (value "1M")
      (footprint "0603")
      (description "Resistor")
      (fields (field (name "Comment") "Res2") (field (name "PUBLISHER") "Altium Limited"))
      (libsource (lib "Miscellaneous Devices") (part "Res2"))
    )
    (comp (ref "R48")
      (value "150R")
      (footprint "0805")
      (description "Resistor")
      (fields (field (name "Comment") "Res2") (field (name "PUBLISHER") "Altium Limited"))
      (libsource (lib "Miscellaneous Devices") (part "Res2"))
    )
    (comp (ref "R49")
      (value "10K")
      (footprint "0805")
      (description "Resistor")
      (fields (field (name "Comment") "Res2") (field (name "PUBLISHER") "Altium Limited"))
      (libsource (lib "霍振飞") (part "Res2"))
    )
    (comp (ref "R50")
      (value "150R")
      (footprint "0805")
      (description "Resistor")
      (fields (field (name "Comment") "Res2") (field (name "PUBLISHER") "Altium Limited"))
      (libsource (lib "Miscellaneous Devices") (part "Res2"))
    )
    (comp (ref "S1")
      (value "SW-DIP4")
      (footprint "BMKG")
      (description "DIP Switch")
      (fields (field (name "PUBLISHER") "Altium Limited"))
      (libsource (lib "主控板原理图") (part "SW-DIP4"))
    )
    (comp (ref "S2")
      (value "SW-PB")
      (footprint "BUTTON")
      (description "Switch")
      (fields (field (name "PUBLISHER") "Altium Limited"))
      (libsource (lib "主控板原理图") (part "SW-PB"))
    )
    (comp (ref "S3")
      (value "SW-PB")
      (footprint "BUTTON")
      (description "Switch")
      (fields (field (name "PUBLISHER") "Altium Limited"))
      (libsource (lib "主控板原理图") (part "SW-PB"))
    )
    (comp (ref "S4")
      (value "SW-PB")
      (footprint "BUTTON")
      (description "Switch")
      (fields (field (name "PUBLISHER") "Altium Limited"))
      (libsource (lib "主控板原理图") (part "SW-PB"))
    )
    (comp (ref "S5")
      (value "SW-PB")
      (footprint "BUTTON")
      (description "Switch")
      (fields (field (name "PUBLISHER") "Altium Limited"))
      (libsource (lib "主控板原理图") (part "SW-PB"))
    )
    (comp (ref "S6")
      (value "SW-PB")
      (footprint "BUTTON")
      (description "Switch")
      (fields (field (name "PUBLISHER") "Altium Limited"))
      (libsource (lib "主控板原理图") (part "SW-PB"))
    )
    (comp (ref "S7")
      (value "SW-PB")
      (footprint "BUTTON")
      (description "Switch")
      (fields (field (name "PUBLISHER") "Altium Limited"))
      (libsource (lib "主控板原理图") (part "SW-PB"))
    )
    (comp (ref "S8")
      (value "zk")
      (footprint "SWITCH-MID")
      (description "Single-Pole, Single-Throw Switch")
      (fields (field (name "PUBLISHER") "Altium Limited"))
      (libsource (lib "Miscellaneous Devices") (part "SW-SPST"))
    )
    (comp (ref "S9")
      (value "SW-PB")
      (footprint "BUTTON")
      (description "按键")
      (fields (field (name "PUBLISHER") "Altium Limited"))
      (libsource (lib "霍振飞") (part "SW-PB"))
    )
    (comp (ref "S10")
      (value "SW-PB")
      (footprint "BUTTON")
      (description "Switch")
      (fields (field (name "PUBLISHER") "Altium Limited"))
      (libsource (lib "主控板原理图") (part "SW-PB"))
    )
    (comp (ref "S11")
      (value "SW-PB")
      (footprint "BUTTON")
      (description "Switch")
      (fields (field (name "PUBLISHER") "Altium Limited"))
      (libsource (lib "主控板原理图") (part "SW-PB"))
    )
    (comp (ref "S12")
      (value "SW-PB")
      (footprint "BUTTON")
      (description "按键")
      (fields (field (name "PUBLISHER") "Altium Limited"))
      (libsource (lib "霍振飞") (part "SW-PB"))
    )
    (comp (ref "U1") (value "MC34063") (footprint "MC34063") (libsource (lib "LY") (part "MC34063")))
    (comp (ref "U2") (value "LM2596-5") (footprint "LM2596") (libsource (lib "主控板原理图") (part "LM2596")))
    (comp (ref "U3") (value "74LS244") (footprint "74ls244DA") (libsource (lib "ly") (part "74LS244")))
    (comp (ref "Y1")
      (value "XTAL")
      (footprint "32.768")
      (description "Crystal Oscillator")
      (fields (field (name "PUBLISHER") "Altium Limited"))
      (libsource (lib "Miscellaneous Devices") (part "XTAL"))
    )
    (comp (ref "Y2")
      (value "XTAL")
      (footprint "32.768")
      (description "Crystal Oscillator")
      (fields (field (name "PUBLISHER") "Altium Limited"))
      (libsource (lib "Miscellaneous Devices") (part "XTAL"))
    )
  )
  (nets
    (net (code "1") (name "/CLKOUT") (class "Default")
      (node (ref "*2") (pin "72") (pinfunction "PTA18/EXTAL_72") (pintype "passive"))
      (node (ref "*3") (pin "3") (pinfunction "CLKOUT_3") (pintype "passive"))
    )
    (net (code "2") (name "/CLKOUT-2") (class "Default")
      (node (ref "*10") (pin "3") (pinfunction "CLKOUT_3") (pintype "passive"))
      (node (ref "*9") (pin "72") (pinfunction "PTA18/EXTAL_72") (pintype "passive"))
    )
    (net (code "3") (name "/EXTAL33") (class "Default")
      (node (ref "*2") (pin "41") (pinfunction "EXTAL33_41") (pintype "passive"))
      (node (ref "C24") (pin "2") (pinfunction "2_2") (pintype "passive"))
      (node (ref "R28") (pin "1") (pinfunction "1_1") (pintype "passive"))
      (node (ref "Y1") (pin "2") (pinfunction "OSC2_2") (pintype "passive"))
    )
    (net (code "4") (name "/EXTAL33-2") (class "Default")
      (node (ref "*9") (pin "41") (pinfunction "EXTAL33_41") (pintype "passive"))
      (node (ref "C59") (pin "2") (pinfunction "2_2") (pintype "passive"))
      (node (ref "R47") (pin "1") (pinfunction "1_1") (pintype "passive"))
      (node (ref "Y2") (pin "2") (pinfunction "OSC2_2") (pintype "passive"))
    )
    (net (code "5") (name "/Motor1 In1") (class "Default")
      (node (ref "Moter1") (pin "1") (pinfunction "1_1") (pintype "passive"))
      (node (ref "U3") (pin "18") (pinfunction "Y1_18") (pintype "passive"))
    )
    (net (code "6") (name "/Motor1 In2") (class "Default")
      (node (ref "Moter1") (pin "2") (pinfunction "2_2") (pintype "passive"))
      (node (ref "U3") (pin "16") (pinfunction "Y2_16") (pintype "passive"))
    )
    (net (code "7") (name "/Motor1 In3") (class "Default")
      (node (ref "Moter1") (pin "3") (pinfunction "3_3") (pintype "passive"))
      (node (ref "U3") (pin "14") (pinfunction "Y3_14") (pintype "passive"))
    )
    (net (code "8") (name "/Motor1 In4") (class "Default")
      (node (ref "Moter1") (pin "4") (pinfunction "4_4") (pintype "passive"))
      (node (ref "U3") (pin "12") (pinfunction "Y4_12") (pintype "passive"))
    )
    (net (code "9") (name "/PTA0") (class "Default")
      (node (ref "*2") (pin "50") (pinfunction "PTA0_50") (pintype "passive"))
      (node (ref "*4") (pin "6") (pinfunction "6_6") (pintype "passive"))
    )
    (net (code "10") (name "/PTA0-2") (class "Default")
      (node (ref "*11") (pin "6") (pinfunction "6_6") (pintype "passive"))
      (node (ref "*9") (pin "50") (pinfunction "PTA0_50") (pintype "passive"))
    )
    (net (code "11") (name "/PTA1") (class "Default")
      (node (ref "*2") (pin "51") (pinfunction "PTA1_51") (pintype "passive"))
      (node (ref "*4") (pin "8") (pinfunction "8_8") (pintype "passive"))
    )
    (net (code "12") (name "/PTA1-2") (class "Default")
      (node (ref "*11") (pin "8") (pinfunction "8_8") (pintype "passive"))
      (node (ref "*9") (pin "51") (pinfunction "PTA1_51") (pintype "passive"))
    )
    (net (code "13") (name "/PTA2") (class "Default")
      (node (ref "*2") (pin "52") (pinfunction "PTA2_52") (pintype "passive"))
      (node (ref "*4") (pin "3") (pinfunction "3_3") (pintype "passive"))
    )
    (net (code "14") (name "/PTA2-2") (class "Default")
      (node (ref "*11") (pin "3") (pinfunction "3_3") (pintype "passive"))
      (node (ref "*9") (pin "52") (pinfunction "PTA2_52") (pintype "passive"))
    )
    (net (code "15") (name "/PTA3") (class "Default")
      (node (ref "*2") (pin "53") (pinfunction "PTA3_53") (pintype "passive"))
      (node (ref "*4") (pin "7") (pinfunction "7_7") (pintype "passive"))
    )
    (net (code "16") (name "/PTA3-2") (class "Default")
      (node (ref "*11") (pin "7") (pinfunction "7_7") (pintype "passive"))
      (node (ref "*9") (pin "53") (pinfunction "PTA3_53") (pintype "passive"))
    )
    (net (code "17") (name "/PTA4") (class "Default")
      (node (ref "*2") (pin "54") (pinfunction "PTA4_54") (pintype "passive"))
      (node (ref "*4") (pin "9") (pinfunction "9_9") (pintype "passive"))
      (node (ref "R5") (pin "1") (pinfunction "1_1") (pintype "passive"))
    )
    (net (code "18") (name "/PTA4-2") (class "Default")
      (node (ref "*11") (pin "9") (pinfunction "9_9") (pintype "passive"))
      (node (ref "*9") (pin "54") (pinfunction "PTA4_54") (pintype "passive"))
      (node (ref "R36") (pin "1") (pinfunction "1_1") (pintype "passive"))
    )
    (net (code "19") (name "/PTA7") (class "Default")
      (node (ref "*2") (pin "59") (pinfunction "PTA7_59") (pintype "passive"))
    )
    (net (code "20") (name "/PTA8") (class "Default")
      (node (ref "*2") (pin "60") (pinfunction "PTA8_60") (pintype "passive"))
    )
    (net (code "21") (name "/PTA10") (class "Default")
      (node (ref "*2") (pin "62") (pinfunction "PTA10_62") (pintype "passive"))
      (node (ref "BMQ2") (pin "3") (pinfunction "A_3") (pintype "passive"))
    )
    (net (code "22") (name "/PTA11") (class "Default")
      (node (ref "*2") (pin "63") (pinfunction "PTA11_63") (pintype "passive"))
      (node (ref "BMQ2") (pin "4") (pinfunction "B_4") (pintype "passive"))
    )
    (net (code "23") (name "/PTA12") (class "Default")
      (node (ref "*2") (pin "64") (pinfunction "PTA12_64") (pintype "passive"))
      (node (ref "BMQ1") (pin "3") (pinfunction "A_3") (pintype "passive"))
    )
    (net (code "24") (name "/PTA13") (class "Default")
      (node (ref "*2") (pin "65") (pinfunction "PTA13_65") (pintype "passive"))
      (node (ref "BMQ1") (pin "4") (pinfunction "B_4") (pintype "passive"))
    )
    (net (code "25") (name "/PTA14") (class "Default")
      (node (ref "*2") (pin "66") (pinfunction "PTA14_66") (pintype "passive"))
      (node (ref "*5") (pin "3") (pinfunction "D1_3") (pintype "passive"))
    )
    (net (code "26") (name "/PTA15") (class "Default")
      (node (ref "*2") (pin "67") (pinfunction "PTA15_67") (pintype "passive"))
      (node (ref "*5") (pin "4") (pinfunction "D2_4") (pintype "passive"))
    )
    (net (code "27") (name "/PTA16") (class "Default")
      (node (ref "*2") (pin "68") (pinfunction "PTA16_68") (pintype "passive"))
      (node (ref "*5") (pin "5") (pinfunction "D3_5") (pintype "passive"))
    )
    (net (code "28") (name "/PTA17") (class "Default")
      (node (ref "*2") (pin "69") (pinfunction "PTA17_69") (pintype "passive"))
      (node (ref "*5") (pin "6") (pinfunction "D4_6") (pintype "passive"))
    )
    (net (code "29") (name "/PTA19") (class "Default")
      (node (ref "*2") (pin "73") (pinfunction "PTA19_73") (pintype "passive"))
      (node (ref "oled1") (pin "6") (pinfunction "DC_6") (pintype "passive"))
    )
    (net (code "30") (name "/PTA19-2") (class "Default")
      (node (ref "*9") (pin "73") (pinfunction "PTA19_73") (pintype "passive"))
      (node (ref "oled2") (pin "6") (pinfunction "DC_6") (pintype "passive"))
    )
    (net (code "31") (name "/PTA24") (class "Default")
      (node (ref "*2") (pin "75") (pinfunction "PTA24_75") (pintype "passive"))
      (node (ref "oled1") (pin "5") (pinfunction "RST_5") (pintype "passive"))
    )
    (net (code "32") (name "/PTA24-2") (class "Default")
      (node (ref "*9") (pin "75") (pinfunction "PTA24_75") (pintype "passive"))
      (node (ref "oled2") (pin "5") (pinfunction "RST_5") (pintype "passive"))
    )
    (net (code "33") (name "/PTA25") (class "Default")
      (node (ref "*1") (pin "10") (pinfunction "SDA_10") (pintype "passive"))
      (node (ref "*2") (pin "76") (pinfunction "PTA25_76") (pintype "passive"))
    )
    (net (code "34") (name "/PTA25-2") (class "Default")
      (node (ref "*12") (pin "10") (pinfunction "SDA_10") (pintype "passive"))
      (node (ref "*9") (pin "76") (pinfunction "PTA25_76") (pintype "passive"))
    )
    (net (code "35") (name "/PTA26") (class "Default")
      (node (ref "*1") (pin "9") (pinfunction "SCL_9") (pintype "passive"))
      (node (ref "*2") (pin "77") (pinfunction "PTA26_77") (pintype "passive"))
    )
    (net (code "36") (name "/PTA26-2") (class "Default")
      (node (ref "*12") (pin "9") (pinfunction "SCL_9") (pintype "passive"))
      (node (ref "*9") (pin "77") (pinfunction "PTA26_77") (pintype "passive"))
    )
    (net (code "37") (name "/PTA27") (class "Default")
      (node (ref "*1") (pin "17") (pinfunction "P_17") (pintype "passive"))
      (node (ref "*2") (pin "78") (pinfunction "PTA27_78") (pintype "passive"))
      (node (ref "R29") (pin "1") (pinfunction "1_1") (pintype "passive"))
    )
    (net (code "38") (name "/PTA27-2") (class "Default")
      (node (ref "*12") (pin "17") (pinfunction "P_17") (pintype "passive"))
      (node (ref "*9") (pin "78") (pinfunction "PTA27_78") (pintype "passive"))
      (node (ref "R48") (pin "1") (pinfunction "1_1") (pintype "passive"))
    )
    (net (code "39") (name "/PTA29") (class "Default")
      (node (ref "*1") (pin "15") (pinfunction "V_15") (pintype "passive"))
      (node (ref "*12") (pin "15") (pinfunction "V_15") (pintype "passive"))
      (node (ref "*2") (pin "80") (pinfunction "PTA29_80") (pintype "passive"))
      (node (ref "R33") (pin "2") (pinfunction "2_2") (pintype "passive"))
    )
    (net (code "40") (name "/PTA29-2") (class "Default")
      (node (ref "*9") (pin "80") (pinfunction "PTA29_80") (pintype "passive"))
      (node (ref "R50") (pin "2") (pinfunction "2_2") (pintype "passive"))
    )
    (net (code "41") (name "/PTB0") (class "Default")
      (node (ref "*1") (pin "1") (pinfunction "D0_1") (pintype "passive"))
      (node (ref "*2") (pin "81") (pinfunction "PTB0_81") (pintype "passive"))
    )
    (net (code "42") (name "/PTB0-2") (class "Default")
      (node (ref "*12") (pin "1") (pinfunction "D0_1") (pintype "passive"))
      (node (ref "*9") (pin "81") (pinfunction "PTB0_81") (pintype "passive"))
    )
    (net (code "43") (name "/PTB1") (class "Default")
      (node (ref "*1") (pin "2") (pinfunction "D1_2") (pintype "passive"))
      (node (ref "*2") (pin "82") (pinfunction "PTB1_82") (pintype "passive"))
    )
    (net (code "44") (name "/PTB1-2") (class "Default")
      (node (ref "*12") (pin "2") (pinfunction "D1_2") (pintype "passive"))
      (node (ref "*9") (pin "82") (pinfunction "PTB1_82") (pintype "passive"))
    )
    (net (code "45") (name "/PTB2") (class "Default")
      (node (ref "*1") (pin "3") (pinfunction "D2_3") (pintype "passive"))
      (node (ref "*2") (pin "83") (pinfunction "PTB2_83") (pintype "passive"))
    )
    (net (code "46") (name "/PTB2-2") (class "Default")
      (node (ref "*12") (pin "3") (pinfunction "D2_3") (pintype "passive"))
      (node (ref "*9") (pin "83") (pinfunction "PTB2_83") (pintype "passive"))
    )
    (net (code "47") (name "/PTB3") (class "Default")
      (node (ref "*1") (pin "4") (pinfunction "D3_4") (pintype "passive"))
      (node (ref "*2") (pin "84") (pinfunction "PTB3_84") (pintype "passive"))
    )
    (net (code "48") (name "/PTB3-2") (class "Default")
      (node (ref "*12") (pin "4") (pinfunction "D3_4") (pintype "passive"))
      (node (ref "*9") (pin "84") (pinfunction "PTB3_84") (pintype "passive"))
    )
    (net (code "49") (name "/PTB4") (class "Default")
      (node (ref "*1") (pin "5") (pinfunction "D4_5") (pintype "passive"))
      (node (ref "*2") (pin "85") (pinfunction "PTB4_85") (pintype "passive"))
    )
    (net (code "50") (name "/PTB4-2") (class "Default")
      (node (ref "*12") (pin "5") (pinfunction "D4_5") (pintype "passive"))
      (node (ref "*9") (pin "85") (pinfunction "PTB4_85") (pintype "passive"))
    )
    (net (code "51") (name "/PTB5") (class "Default")
      (node (ref "*1") (pin "6") (pinfunction "D5_6") (pintype "passive"))
      (node (ref "*2") (pin "86") (pinfunction "PTB5_86") (pintype "passive"))
    )
    (net (code "52") (name "/PTB5-2") (class "Default")
      (node (ref "*12") (pin "6") (pinfunction "D5_6") (pintype "passive"))
      (node (ref "*9") (pin "86") (pinfunction "PTB5_86") (pintype "passive"))
    )
    (net (code "53") (name "/PTB6") (class "Default")
      (node (ref "*1") (pin "7") (pinfunction "D6_7") (pintype "passive"))
      (node (ref "*2") (pin "87") (pinfunction "PTB6_87") (pintype "passive"))
    )
    (net (code "54") (name "/PTB6-2") (class "Default")
      (node (ref "*12") (pin "7") (pinfunction "D6_7") (pintype "passive"))
      (node (ref "*9") (pin "87") (pinfunction "PTB6_87") (pintype "passive"))
    )
    (net (code "55") (name "/PTB7") (class "Default")
      (node (ref "*1") (pin "8") (pinfunction "D7_8") (pintype "passive"))
      (node (ref "*2") (pin "88") (pinfunction "PTB7_88") (pintype "passive"))
    )
    (net (code "56") (name "/PTB7-2") (class "Default")
      (node (ref "*12") (pin "8") (pinfunction "D7_8") (pintype "passive"))
      (node (ref "*9") (pin "88") (pinfunction "PTB7_88") (pintype "passive"))
    )
    (net (code "57") (name "/PTB10") (class "Default")
      (node (ref "*2") (pin "91") (pinfunction "PTB10_91") (pintype "passive"))
    )
    (net (code "58") (name "/PTB11") (class "Default")
      (node (ref "*2") (pin "92") (pinfunction "PTB11_92") (pintype "passive"))
    )
    (net (code "59") (name "/PTB16") (class "Default")
      (node (ref "*2") (pin "95") (pinfunction "PTB16_95") (pintype "passive"))
      (node (ref "R1") (pin "1") (pinfunction "1_1") (pintype "passive"))
      (node (ref "S1") (pin "8") (pinfunction "8_8") (pintype "passive"))
    )
    (net (code "60") (name "/PTB17") (class "Default")
      (node (ref "*2") (pin "96") (pinfunction "PTB17_96") (pintype "passive"))
      (node (ref "R2") (pin "1") (pinfunction "1_1") (pintype "passive"))
      (node (ref "S1") (pin "7") (pinfunction "7_7") (pintype "passive"))
    )
    (net (code "61") (name "/PTB18") (class "Default")
      (node (ref "*2") (pin "97") (pinfunction "PTB18_97") (pintype "passive"))
      (node (ref "R3") (pin "1") (pinfunction "1_1") (pintype "passive"))
      (node (ref "S1") (pin "6") (pinfunction "6_6") (pintype "passive"))
    )
    (net (code "62") (name "/PTB19") (class "Default")
      (node (ref "*2") (pin "98") (pinfunction "PTB19_98") (pintype "passive"))
      (node (ref "R4") (pin "2") (pinfunction "2_2") (pintype "passive"))
      (node (ref "S1") (pin "5") (pinfunction "5_5") (pintype "passive"))
    )
    (net (code "63") (name "/PTB21") (class "Default")
      (node (ref "*2") (pin "100") (pinfunction "PTB21_100") (pintype "passive"))
      (node (ref "oled1") (pin "3") (pinfunction "SCL_3") (pintype "passive"))
    )
    (net (code "64") (name "/PTB21-2") (class "Default")
      (node (ref "*9") (pin "100") (pinfunction "PTB21_100") (pintype "passive"))
      (node (ref "oled2") (pin "3") (pinfunction "SCL_3") (pintype "passive"))
    )
    (net (code "65") (name "/PTB22") (class "Default")
      (node (ref "*2") (pin "101") (pinfunction "PTB22_101") (pintype "passive"))
      (node (ref "oled1") (pin "4") (pinfunction "SDA_4") (pintype "passive"))
    )
    (net (code "66") (name "/PTB22-2") (class "Default")
      (node (ref "*9") (pin "101") (pinfunction "PTB22_101") (pintype "passive"))
      (node (ref "oled2") (pin "4") (pinfunction "SDA_4") (pintype "passive"))
    )
    (net (code "67") (name "/PTC0") (class "Default")
      (node (ref "*2") (pin "103") (pinfunction "PTC0_103") (pintype "passive"))
    )
    (net (code "68") (name "/PTC1") (class "Default")
      (node (ref "*2") (pin "104") (pinfunction "PTC1_104") (pintype "passive"))
    )
    (net (code "69") (name "/PTC2") (class "Default")
      (node (ref "*2") (pin "105") (pinfunction "PTC2_105") (pintype "passive"))
      (node (ref "*7") (pin "3") (pinfunction "PWM_3") (pintype "passive"))
    )
    (net (code "70") (name "/PTC4") (class "Default")
      (node (ref "*2") (pin "109") (pinfunction "PTC4_109") (pintype "passive"))
      (node (ref "*8") (pin "3") (pinfunction "SCL_3") (pintype "passive"))
    )
    (net (code "71") (name "/PTC5") (class "Default")
      (node (ref "*2") (pin "110") (pinfunction "PTC5_110") (pintype "passive"))
      (node (ref "*8") (pin "4") (pinfunction "SDA_4") (pintype "passive"))
    )
    (net (code "72") (name "/PTC6") (class "Default")
      (node (ref "*2") (pin "111") (pinfunction "PTC6_111") (pintype "passive"))
      (node (ref "*8") (pin "5") (pinfunction "DNC_5") (pintype "passive"))
    )
    (net (code "73") (name "/PTC7") (class "Default")
      (node (ref "*2") (pin "112") (pinfunction "PTC7_112") (pintype "passive"))
      (node (ref "*8") (pin "6") (pinfunction "GN2_6") (pintype "passive"))
    )
    (net (code "74") (name "/PTC8") (class "Default")
      (node (ref "*2") (pin "113") (pinfunction "PTC8_113") (pintype "passive"))
      (node (ref "*8") (pin "7") (pinfunction "XSH_7") (pintype "passive"))
    )
    (net (code "75") (name "/PTC9") (class "Default")
      (node (ref "*2") (pin "114") (pinfunction "PTC9_114") (pintype "passive"))
      (node (ref "*8") (pin "8") (pinfunction "INT_8") (pintype "passive"))
    )
    (net (code "76") (name "/PTC11") (class "Default")
      (node (ref "*2") (pin "116") (pinfunction "PTC11_116") (pintype "passive"))
      (node (ref "R13") (pin "1") (pinfunction "1_1") (pintype "passive"))
      (node (ref "S7") (pin "2") (pinfunction "2_2") (pintype "passive"))
    )
    (net (code "77") (name "/PTC12") (class "Default")
      (node (ref "*2") (pin "117") (pinfunction "PTC12_117") (pintype "passive"))
      (node (ref "R10") (pin "1") (pinfunction "1_1") (pintype "passive"))
      (node (ref "S4") (pin "2") (pinfunction "2_2") (pintype "passive"))
    )
    (net (code "78") (name "/PTD1") (class "Default")
      (node (ref "*2") (pin "128") (pinfunction "PTD1_128") (pintype "passive"))
      (node (ref "R9") (pin "1") (pinfunction "1_1") (pintype "passive"))
      (node (ref "S3") (pin "2") (pinfunction "2_2") (pintype "passive"))
    )
    (net (code "79") (name "/PTD2") (class "Default")
      (node (ref "*2") (pin "129") (pinfunction "PTD2_129") (pintype "passive"))
      (node (ref "R12") (pin "1") (pinfunction "1_1") (pintype "passive"))
      (node (ref "S6") (pin "2") (pinfunction "2_2") (pintype "passive"))
    )
    (net (code "80") (name "/PTD7") (class "Default")
      (node (ref "*2") (pin "136") (pinfunction "PTD7_136") (pintype "passive"))
    )
    (net (code "81") (name "/PTD8") (class "Default")
      (node (ref "*2") (pin "137") (pinfunction "PTD8_137") (pintype "passive"))
    )
    (net (code "82") (name "/PTD9") (class "Default")
      (node (ref "*2") (pin "138") (pinfunction "PTD9_138") (pintype "passive"))
    )
    (net (code "83") (name "/PTD10") (class "Default")
      (node (ref "*2") (pin "139") (pinfunction "PTD10_139") (pintype "passive"))
      (node (ref "R8") (pin "1") (pinfunction "1_1") (pintype "passive"))
      (node (ref "S2") (pin "2") (pinfunction "2_2") (pintype "passive"))
    )
    (net (code "84") (name "/PTD11") (class "Default")
      (node (ref "*2") (pin "140") (pinfunction "PTD11_140") (pintype "passive"))
      (node (ref "R11") (pin "1") (pinfunction "1_1") (pintype "passive"))
      (node (ref "S5") (pin "2") (pinfunction "2_2") (pintype "passive"))
    )
    (net (code "85") (name "/PTD12") (class "Default")
      (node (ref "*2") (pin "141") (pinfunction "PTD12_141") (pintype "passive"))
      (node (ref "R19") (pin "2") (pinfunction "2_2") (pintype "passive"))
    )
    (net (code "86") (name "/PTD13") (class "Default")
      (node (ref "*2") (pin "142") (pinfunction "PTD13_142") (pintype "passive"))
      (node (ref "R20") (pin "2") (pinfunction "2_2") (pintype "passive"))
    )
    (net (code "87") (name "/PTD14") (class "Default")
      (node (ref "*2") (pin "143") (pinfunction "PTD14_143") (pintype "passive"))
      (node (ref "R22") (pin "2") (pinfunction "2_2") (pintype "passive"))
    )
    (net (code "88") (name "/PTD14-2") (class "Default")
      (node (ref "*9") (pin "143") (pinfunction "PTD14_143") (pintype "passive"))
      (node (ref "R41") (pin "2") (pinfunction "2_2") (pintype "passive"))
    )
    (net (code "89") (name "/PTD15") (class "Default")
      (node (ref "*2") (pin "144") (pinfunction "PTD15_144") (pintype "passive"))
      (node (ref "R24") (pin "2") (pinfunction "2_2") (pintype "passive"))
    )
    (net (code "90") (name "/PTD15-2") (class "Default")
      (node (ref "*9") (pin "144") (pinfunction "PTD15_144") (pintype "passive"))
      (node (ref "R40") (pin "2") (pinfunction "2_2") (pintype "passive"))
    )
    (net (code "91") (name "/PTE0") (class "Default")
      (node (ref "*2") (pin "1") (pinfunction "PTE0_1") (pintype "passive"))
      (node (ref "*6") (pin "4") (pinfunction "SDA_4") (pintype "passive"))
    )
    (net (code "92") (name "/PTE1") (class "Default")
      (node (ref "*2") (pin "2") (pinfunction "PTE1_2") (pintype "passive"))
      (node (ref "*6") (pin "3") (pinfunction "SCL_3") (pintype "passive"))
    )
    (net (code "93") (name "/PTE2") (class "Default")
      (node (ref "*2") (pin "3") (pinfunction "PTE2_3") (pintype "passive"))
      (node (ref "R31") (pin "1") (pinfunction "1_1") (pintype "passive"))
    )
    (net (code "94") (name "/PTE5") (class "Default")
      (node (ref "*2") (pin "8") (pinfunction "PTE5_8") (pintype "passive"))
      (node (ref "U3") (pin "2") (pinfunction "A1_2") (pintype "passive"))
    )
    (net (code "95") (name "/PTE6") (class "Default")
      (node (ref "*2") (pin "9") (pinfunction "PTE6_9") (pintype "passive"))
      (node (ref "U3") (pin "4") (pinfunction "A2_4") (pintype "passive"))
    )
    (net (code "96") (name "/PTE7") (class "Default")
      (node (ref "*2") (pin "10") (pinfunction "PTE7_10") (pintype "passive"))
      (node (ref "U3") (pin "6") (pinfunction "A3_6") (pintype "passive"))
    )
    (net (code "97") (name "/PTE8") (class "Default")
      (node (ref "*2") (pin "11") (pinfunction "PTE8_11") (pintype "passive"))
      (node (ref "blue1") (pin "4") (pinfunction "RXD_4") (pintype "passive"))
    )
    (net (code "98") (name "/PTE9") (class "Default")
      (node (ref "*2") (pin "12") (pinfunction "PTE9_12") (pintype "passive"))
      (node (ref "blue1") (pin "3") (pinfunction "TXD_3") (pintype "passive"))
    )
    (net (code "99") (name "/PTE10") (class "Default")
      (node (ref "*2") (pin "13") (pinfunction "PTE10_13") (pintype "passive"))
      (node (ref "U3") (pin "8") (pinfunction "A4_8") (pintype "passive"))
    )
    (net (code "100") (name "/PTE24") (class "Default")
      (node (ref "*2") (pin "45") (pinfunction "PTE24_45") (pintype "passive"))
    )
    (net (code "101") (name "/PTE25") (class "Default")
      (node (ref "*2") (pin "46") (pinfunction "PTE25_46") (pintype "passive"))
    )
    (net (code "102") (name "/PTE26-2") (class "Default")
      (node (ref "*9") (pin "47") (pinfunction "PTE26_47") (pintype "passive"))
      (node (ref "R44") (pin "1") (pinfunction "1_1") (pintype "passive"))
      (node (ref "S11") (pin "2") (pinfunction "2_2") (pintype "passive"))
    )
    (net (code "103") (name "/PTE27-2") (class "Default")
      (node (ref "*9") (pin "48") (pinfunction "PTE27_48") (pintype "passive"))
      (node (ref "R43") (pin "1") (pinfunction "1_1") (pintype "passive"))
      (node (ref "S10") (pin "2") (pinfunction "2_2") (pintype "passive"))
    )
    (net (code "104") (name "/RESET") (class "Default")
      (node (ref "*2") (pin "74") (pinfunction "RESET_b_74") (pintype "passive"))
      (node (ref "*4") (pin "2") (pinfunction "2_2") (pintype "passive"))
      (node (ref "C26") (pin "2") (pinfunction "2_2") (pintype "passive"))
      (node (ref "R32") (pin "2") (pinfunction "2_2") (pintype "passive"))
      (node (ref "S9") (pin "2") (pinfunction "2_2") (pintype "passive"))
    )
    (net (code "105") (name "/RESET-2") (class "Default")
      (node (ref "*11") (pin "2") (pinfunction "2_2") (pintype "passive"))
      (node (ref "*9") (pin "74") (pinfunction "RESET_b_74") (pintype "passive"))
      (node (ref "C61") (pin "2") (pinfunction "2_2") (pintype "passive"))
      (node (ref "R49") (pin "2") (pinfunction "2_2") (pintype "passive"))
      (node (ref "S12") (pin "2") (pinfunction "2_2") (pintype "passive"))
    )
    (net (code "106") (name "/XTAL32") (class "Default")
      (node (ref "*2") (pin "40") (pinfunction "XTAL32_40") (pintype "passive"))
      (node (ref "C20") (pin "2") (pinfunction "2_2") (pintype "passive"))
      (node (ref "R28") (pin "2") (pinfunction "2_2") (pintype "passive"))
      (node (ref "Y1") (pin "1") (pinfunction "OSC1_1") (pintype "passive"))
    )
    (net (code "107") (name "/XTAL32-2") (class "Default")
      (node (ref "*9") (pin "40") (pinfunction "XTAL32_40") (pintype "passive"))
      (node (ref "C58") (pin "2") (pinfunction "2_2") (pintype "passive"))
      (node (ref "R47") (pin "2") (pinfunction "2_2") (pintype "passive"))
      (node (ref "Y2") (pin "1") (pinfunction "OSC1_1") (pintype "passive"))
    )
    (net (code "108") (name "3V3-1") (class "Default")
      (node (ref "*2") (pin "108") (pinfunction "VDD_108") (pintype "passive"))
      (node (ref "*2") (pin "122") (pinfunction "VDD_122") (pintype "passive"))
      (node (ref "*2") (pin "135") (pinfunction "VDD_135") (pintype "passive"))
      (node (ref "*2") (pin "16") (pinfunction "VDD_16") (pintype "passive"))
      (node (ref "*2") (pin "43") (pinfunction "VDD_43") (pintype "passive"))
      (node (ref "*2") (pin "5") (pinfunction "VDD_5") (pintype "passive"))
      (node (ref "*2") (pin "56") (pinfunction "VDD_56") (pintype "passive"))
      (node (ref "*2") (pin "70") (pinfunction "VDD_70") (pintype "passive"))
      (node (ref "*2") (pin "94") (pinfunction "VDD_94") (pintype "passive"))
      (node (ref "*4") (pin "10") (pinfunction "10_10") (pintype "passive"))
      (node (ref "3") (pin "2") (pinfunction "OUT_2") (pintype "open_emitter"))
      (node (ref "C13") (pin "1") (pinfunction "1_1") (pintype "passive"))
      (node (ref "C25") (pin "1") (pinfunction "1_1") (pintype "passive"))
      (node (ref "C29") (pin "1") (pinfunction "1_1") (pintype "passive"))
      (node (ref "C3") (pin "1") (pinfunction "1_1") (pintype "passive"))
      (node (ref "C35") (pin "2") (pinfunction "2_2") (pintype "passive"))
      (node (ref "C36") (pin "1") (pinfunction "1_1") (pintype "passive"))
      (node (ref "C37") (pin "1") (pinfunction "1_1") (pintype "passive"))
      (node (ref "C4") (pin "2") (pinfunction "2_2") (pintype "passive"))
      (node (ref "C42") (pin "1") (pinfunction "1_1") (pintype "passive"))
      (node (ref "C6") (pin "2") (pinfunction "2_2") (pintype "passive"))
      (node (ref "C7") (pin "1") (pinfunction "1_1") (pintype "passive"))
      (node (ref "D2") (pin "1") (pinfunction "A_1") (pintype "passive"))
      (node (ref "D3") (pin "1") (pinfunction "A_1") (pintype "passive"))
      (node (ref "D4") (pin "1") (pinfunction "A_1") (pintype "passive"))
      (node (ref "D5") (pin "1") (pinfunction "A_1") (pintype "passive"))
      (node (ref "D6") (pin "1") (pinfunction "A_1") (pintype "passive"))
      (node (ref "L1") (pin "1") (pinfunction "1_1") (pintype "passive"))
      (node (ref "L3") (pin "1") (pinfunction "1_1") (pintype "passive"))
      (node (ref "R14") (pin "1") (pinfunction "1_1") (pintype "passive"))
      (node (ref "R18") (pin "1") (pinfunction "1_1") (pintype "passive"))
      (node (ref "R23") (pin "1") (pinfunction "1_1") (pintype "passive"))
      (node (ref "R32") (pin "1") (pinfunction "1_1") (pintype "passive"))
      (node (ref "R5") (pin "2") (pinfunction "2_2") (pintype "passive"))
    )
    (net (code "109") (name "3V3-2") (class "Default")
      (node (ref "*11") (pin "10") (pinfunction "10_10") (pintype "passive"))
      (node (ref "*9") (pin "108") (pinfunction "VDD_108") (pintype "passive"))
      (node (ref "*9") (pin "122") (pinfunction "VDD_122") (pintype "passive"))
      (node (ref "*9") (pin "135") (pinfunction "VDD_135") (pintype "passive"))
      (node (ref "*9") (pin "16") (pinfunction "VDD_16") (pintype "passive"))
      (node (ref "*9") (pin "43") (pinfunction "VDD_43") (pintype "passive"))
      (node (ref "*9") (pin "5") (pinfunction "VDD_5") (pintype "passive"))
      (node (ref "*9") (pin "70") (pinfunction "VDD_70") (pintype "passive"))
      (node (ref "*9") (pin "94") (pinfunction "VDD_94") (pintype "passive"))
      (node (ref "4") (pin "2") (pinfunction "OUT_2") (pintype "open_emitter"))
      (node (ref "C38") (pin "1") (pinfunction "1_1") (pintype "passive"))
      (node (ref "C41") (pin "2") (pinfunction "2_2") (pintype "passive"))
      (node (ref "C45") (pin "1") (pinfunction "1_1") (pintype "passive"))
      (node (ref "C46") (pin "2") (pinfunction "2_2") (pintype "passive"))
      (node (ref "C47") (pin "2") (pinfunction "2_2") (pintype "passive"))
      (node (ref "C52") (pin "1") (pinfunction "1_1") (pintype "passive"))
      (node (ref "C60") (pin "1") (pinfunction "1_1") (pintype "passive"))
      (node (ref "C62") (pin "1") (pinfunction "1_1") (pintype "passive"))
      (node (ref "C63") (pin "1") (pinfunction "1_1") (pintype "passive"))
      (node (ref "C64") (pin "1") (pinfunction "1_1") (pintype "passive"))
      (node (ref "D11") (pin "1") (pinfunction "A_1") (pintype "passive"))
      (node (ref "D12") (pin "1") (pinfunction "A_1") (pintype "passive"))
      (node (ref "D13") (pin "1") (pinfunction "A_1") (pintype "passive"))
      (node (ref "L6") (pin "1") (pinfunction "1_1") (pintype "passive"))
      (node (ref "L7") (pin "1") (pinfunction "1_1") (pintype "passive"))
      (node (ref "L8") (pin "1") (pinfunction "1_1") (pintype "passive"))
      (node (ref "R36") (pin "2") (pinfunction "2_2") (pintype "passive"))
      (node (ref "R37") (pin "1") (pinfunction "1_1") (pintype "passive"))
      (node (ref "R39") (pin "1") (pinfunction "1_1") (pintype "passive"))
      (node (ref "R43") (pin "2") (pinfunction "2_2") (pintype "passive"))
      (node (ref "R44") (pin "2") (pinfunction "2_2") (pintype "passive"))
      (node (ref "R45") (pin "1") (pinfunction "1_1") (pintype "passive"))
      (node (ref "R49") (pin "1") (pinfunction "1_1") (pintype "passive"))
    )
    (net (code "110") (name "3V3-3") (class "Default")
      (node (ref "2") (pin "2") (pinfunction "OUT_2") (pintype "open_emitter"))
      (node (ref "C28") (pin "1") (pinfunction "1_1") (pintype "passive"))
      (node (ref "C32") (pin "2") (pinfunction "2_2") (pintype "passive"))
      (node (ref "D9") (pin "1") (pinfunction "A_1") (pintype "passive"))
      (node (ref "R1") (pin "2") (pinfunction "2_2") (pintype "passive"))
      (node (ref "R10") (pin "2") (pinfunction "2_2") (pintype "passive"))
      (node (ref "R11") (pin "2") (pinfunction "2_2") (pintype "passive"))
      (node (ref "R12") (pin "2") (pinfunction "2_2") (pintype "passive"))
      (node (ref "R13") (pin "2") (pinfunction "2_2") (pintype "passive"))
      (node (ref "R2") (pin "2") (pinfunction "2_2") (pintype "passive"))
      (node (ref "R3") (pin "2") (pinfunction "2_2") (pintype "passive"))
      (node (ref "R4") (pin "1") (pinfunction "1_1") (pintype "passive"))
      (node (ref "R8") (pin "2") (pinfunction "2_2") (pintype "passive"))
      (node (ref "R9") (pin "2") (pinfunction "2_2") (pintype "passive"))
      (node (ref "bell1") (pin "1") (pinfunction "A_1") (pintype "passive"))
    )
    (net (code "111") (name "5V") (class "Default")
      (node (ref "*1") (pin "20") (pinfunction "5V_20") (pintype "passive"))
      (node (ref "*12") (pin "20") (pinfunction "5V_20") (pintype "passive"))
      (node (ref "*5") (pin "2") (pinfunction "5V_2") (pintype "passive"))
      (node (ref "*6") (pin "1") (pinfunction "5V_1") (pintype "passive"))
      (node (ref "*8") (pin "1") (pinfunction "VCC_1") (pintype "passive"))
      (node (ref "2") (pin "3") (pinfunction "IN_3") (pintype "open_emitter"))
      (node (ref "3") (pin "3") (pinfunction "IN_3") (pintype "open_emitter"))
      (node (ref "4") (pin "3") (pinfunction "IN_3") (pintype "open_emitter"))
      (node (ref "BMQ1") (pin "2") (pinfunction "VCC_2") (pintype "passive"))
      (node (ref "BMQ2") (pin "2") (pinfunction "VCC_2") (pintype "passive"))
      (node (ref "C23") (pin "1") (pinfunction "1_1") (pintype "passive"))
      (node (ref "C27") (pin "2") (pinfunction "2_2") (pintype "passive"))
      (node (ref "C30") (pin "2") (pinfunction "2_2") (pintype "passive"))
      (node (ref "C31") (pin "2") (pinfunction "2_2") (pintype "passive"))
      (node (ref "C33") (pin "2") (pinfunction "2_2") (pintype "passive"))
      (node (ref "C34") (pin "2") (pinfunction "2_2") (pintype "passive"))
      (node (ref "C39") (pin "2") (pinfunction "2_2") (pintype "passive"))
      (node (ref "C40") (pin "2") (pinfunction "2_2") (pintype "passive"))
      (node (ref "D10") (pin "1") (pinfunction "A_1") (pintype "passive"))
      (node (ref "DY2") (pin "2") (pinfunction "7.2V_2") (pintype "passive"))
      (node (ref "L5") (pin "2") (pinfunction "2_2") (pintype "passive"))
      (node (ref "U2") (pin "4") (pinfunction "FeedBack_4") (pintype "passive"))
      (node (ref "U3") (pin "20") (pinfunction "20_20") (pintype "passive"))
      (node (ref "blue1") (pin "1") (pinfunction "5V_1") (pintype "passive"))
      (node (ref "oled1") (pin "2") (pinfunction "3V3_2") (pintype "passive"))
      (node (ref "oled2") (pin "2") (pinfunction "3V3_2") (pintype "passive"))
    )
    (net (code "112") (name "6V") (class "Default")
      (node (ref "*7") (pin "2") (pinfunction "5V_2") (pintype "passive"))
      (node (ref "1") (pin "2") (pinfunction "OUT_2") (pintype "open_emitter"))
      (node (ref "C19") (pin "2") (pinfunction "2_2") (pintype "passive"))
      (node (ref "R27") (pin "2") (pinfunction "2_2") (pintype "passive"))
    )
    (net (code "113") (name "7V2") (class "Default")
      (node (ref "1") (pin "3") (pinfunction "IN_3") (pintype "open_emitter"))
      (node (ref "C21") (pin "2") (pinfunction "2_2") (pintype "passive"))
      (node (ref "C22") (pin "1") (pinfunction "1_1") (pintype "passive"))
      (node (ref "C9") (pin "1") (pinfunction "1_1") (pintype "passive"))
      (node (ref "CON2") (pin "1") (pinfunction "1_1") (pintype "passive"))
      (node (ref "DY1") (pin "2") (pinfunction "7.2V_2") (pintype "passive"))
      (node (ref "R25") (pin "2") (pinfunction "2_2") (pintype "passive"))
      (node (ref "R6") (pin "2") (pinfunction "2_2") (pintype "passive"))
      (node (ref "S8") (pin "2") (pinfunction "NO_2") (pintype "passive"))
      (node (ref "U1") (pin "6") (pinfunction "VCC_6") (pintype "passive"))
      (node (ref "U2") (pin "1") (pinfunction "IN_1") (pintype "passive"))
    )
    (net (code "114") (name "12V") (class "Default")
      (node (ref "C5") (pin "1") (pinfunction "1_1") (pintype "passive"))
      (node (ref "D1") (pin "2") (pinfunction "K_2") (pintype "passive"))
      (node (ref "Moter1") (pin "5") (pinfunction "12V_5") (pintype "passive"))
      (node (ref "R16") (pin "2") (pinfunction "2_2") (pintype "passive"))
    )
    (net (code "115") (name "GND") (class "Default")
      (node (ref "*1") (pin "11") (pinfunction "GND_11") (pintype "passive"))
      (node (ref "*10") (pin "2") (pinfunction "GND_2") (pintype "passive"))
      (node (ref "*11") (pin "5") (pinfunction "5_5") (pintype "passive"))
      (node (ref "*12") (pin "11") (pinfunction "GND_11") (pintype "passive"))
      (node (ref "*2") (pin "107") (pinfunction "VSS_107") (pintype "passive"))
      (node (ref "*2") (pin "121") (pinfunction "VSS_121") (pintype "passive"))
      (node (ref "*2") (pin "134") (pinfunction "VSS_134") (pintype "passive"))
      (node (ref "*2") (pin "17") (pinfunction "VSS_17") (pintype "passive"))
      (node (ref "*2") (pin "18") (pinfunction "VSS_18") (pintype "passive"))
      (node (ref "*2") (pin "44") (pinfunction "VSS_44") (pintype "passive"))
      (node (ref "*2") (pin "57") (pinfunction "VSS_57") (pintype "passive"))
      (node (ref "*2") (pin "6") (pinfunction "VSS_6") (pintype "passive"))
      (node (ref "*2") (pin "71") (pinfunction "VSS_71") (pintype "passive"))
      (node (ref "*2") (pin "93") (pinfunction "VSS_93") (pintype "passive"))
      (node (ref "*3") (pin "2") (pinfunction "GND_2") (pintype "passive"))
      (node (ref "*4") (pin "5") (pinfunction "5_5") (pintype "passive"))
      (node (ref "*5") (pin "1") (pinfunction "GND_1") (pintype "passive"))
      (node (ref "*6") (pin "2") (pinfunction "GND_2") (pintype "passive"))
      (node (ref "*7") (pin "1") (pinfunction "GND_1") (pintype "passive"))
      (node (ref "*8") (pin "2") (pinfunction "GND_2") (pintype "passive"))
      (node (ref "*9") (pin "107") (pinfunction "VSS_107") (pintype "passive"))
      (node (ref "*9") (pin "121") (pinfunction "VSS_121") (pintype "passive"))
      (node (ref "*9") (pin "134") (pinfunction "VSS_134") (pintype "passive"))
      (node (ref "*9") (pin "17") (pinfunction "VSS_17") (pintype "passive"))
      (node (ref "*9") (pin "18") (pinfunction "VSS_18") (pintype "passive"))
      (node (ref "*9") (pin "44") (pinfunction "VSS_44") (pintype "passive"))
      (node (ref "*9") (pin "57") (pinfunction "VSS_57") (pintype "passive"))
      (node (ref "*9") (pin "6") (pinfunction "VSS_6") (pintype "passive"))
      (node (ref "*9") (pin "71") (pinfunction "VSS_71") (pintype "passive"))
      (node (ref "*9") (pin "93") (pinfunction "VSS_93") (pintype "passive"))
      (node (ref "2") (pin "1") (pinfunction "GND_1") (pintype "open_emitter"))
      (node (ref "3") (pin "1") (pinfunction "GND_1") (pintype "open_emitter"))
      (node (ref "4") (pin "1") (pinfunction "GND_1") (pintype "open_emitter"))
      (node (ref "BMQ1") (pin "1") (pinfunction "GND_1") (pintype "passive"))
      (node (ref "BMQ2") (pin "1") (pinfunction "GND_1") (pintype "passive"))
      (node (ref "C1") (pin "1") (pinfunction "1_1") (pintype "passive"))
      (node (ref "C10") (pin "1") (pinfunction "1_1") (pintype "passive"))
      (node (ref "C11") (pin "1") (pinfunction "1_1") (pintype "passive"))
      (node (ref "C12") (pin "1") (pinfunction "1_1") (pintype "passive"))
      (node (ref "C13") (pin "2") (pinfunction "2_2") (pintype "passive"))
      (node (ref "C18") (pin "1") (pinfunction "1_1") (pintype "passive"))
      (node (ref "C19") (pin "1") (pinfunction "1_1") (pintype "passive"))
      (node (ref "C2") (pin "1") (pinfunction "1_1") (pintype "passive"))
      (node (ref "C20") (pin "1") (pinfunction "1_1") (pintype "passive"))
      (node (ref "C21") (pin "1") (pinfunction "1_1") (pintype "passive"))
      (node (ref "C22") (pin "2") (pinfunction "2_2") (pintype "passive"))
      (node (ref "C23") (pin "2") (pinfunction "2_2") (pintype "passive"))
      (node (ref "C24") (pin "1") (pinfunction "1_1") (pintype "passive"))
      (node (ref "C25") (pin "2") (pinfunction "2_2") (pintype "passive"))
      (node (ref "C26") (pin "1") (pinfunction "1_1") (pintype "passive"))
      (node (ref "C27") (pin "1") (pinfunction "1_1") (pintype "passive"))
      (node (ref "C28") (pin "2") (pinfunction "2_2") (pintype "passive"))
      (node (ref "C29") (pin "2") (pinfunction "2_2") (pintype "passive"))
      (node (ref "C3") (pin "2") (pinfunction "2_2") (pintype "passive"))
      (node (ref "C30") (pin "1") (pinfunction "1_1") (pintype "passive"))
      (node (ref "C31") (pin "1") (pinfunction "1_1") (pintype "passive"))
      (node (ref "C32") (pin "1") (pinfunction "1_1") (pintype "passive"))
      (node (ref "C33") (pin "1") (pinfunction "1_1") (pintype "passive"))
      (node (ref "C34") (pin "1") (pinfunction "1_1") (pintype "passive"))
      (node (ref "C35") (pin "1") (pinfunction "1_1") (pintype "passive"))
      (node (ref "C36") (pin "2") (pinfunction "2_2") (pintype "passive"))
      (node (ref "C37") (pin "2") (pinfunction "2_2") (pintype "passive"))
      (node (ref "C38") (pin "2") (pinfunction "2_2") (pintype "passive"))
      (node (ref "C39") (pin "1") (pinfunction "1_1") (pintype "passive"))
      (node (ref "C4") (pin "1") (pinfunction "1_1") (pintype "passive"))
      (node (ref "C40") (pin "1") (pinfunction "1_1") (pintype "passive"))
      (node (ref "C41") (pin "1") (pinfunction "1_1") (pintype "passive"))
      (node (ref "C42") (pin "2") (pinfunction "2_2") (pintype "passive"))
      (node (ref "C43") (pin "1") (pinfunction "1_1") (pintype "passive"))
      (node (ref "C44") (pin "1") (pinfunction "1_1") (pintype "passive"))
      (node (ref "C45") (pin "2") (pinfunction "2_2") (pintype "passive"))
      (node (ref "C46") (pin "1") (pinfunction "1_1") (pintype "passive"))
      (node (ref "C47") (pin "1") (pinfunction "1_1") (pintype "passive"))
      (node (ref "C48") (pin "2") (pinfunction "2_2") (pintype "passive"))
      (node (ref "C49") (pin "1") (pinfunction "1_1") (pintype "passive"))
      (node (ref "C5") (pin "2") (pinfunction "2_2") (pintype "passive"))
      (node (ref "C50") (pin "1") (pinfunction "1_1") (pintype "passive"))
      (node (ref "C51") (pin "1") (pinfunction "1_1") (pintype "passive"))
      (node (ref "C52") (pin "2") (pinfunction "2_2") (pintype "passive"))
      (node (ref "C57") (pin "1") (pinfunction "1_1") (pintype "passive"))
      (node (ref "C58") (pin "1") (pinfunction "1_1") (pintype "passive"))
      (node (ref "C59") (pin "1") (pinfunction "1_1") (pintype "passive"))
      (node (ref "C6") (pin "1") (pinfunction "1_1") (pintype "passive"))
      (node (ref "C60") (pin "2") (pinfunction "2_2") (pintype "passive"))
      (node (ref "C61") (pin "1") (pinfunction "1_1") (pintype "passive"))
      (node (ref "C62") (pin "2") (pinfunction "2_2") (pintype "passive"))
      (node (ref "C63") (pin "2") (pinfunction "2_2") (pintype "passive"))
      (node (ref "C64") (pin "2") (pinfunction "2_2") (pintype "passive"))
      (node (ref "C7") (pin "2") (pinfunction "2_2") (pintype "passive"))
      (node (ref "C8") (pin "2") (pinfunction "2_2") (pintype "passive"))
      (node (ref "C9") (pin "2") (pinfunction "2_2") (pintype "passive"))
      (node (ref "CON1") (pin "2") (pinfunction "2_2") (pintype "passive"))
      (node (ref "CON2") (pin "2") (pinfunction "2_2") (pintype "passive"))
      (node (ref "D7") (pin "2") (pinfunction "K_2") (pintype "passive"))
      (node (ref "D8") (pin "2") (pinfunction "K_2") (pintype "passive"))
      (node (ref "DY1") (pin "1") (pinfunction "GND_1") (pintype "passive"))
      (node (ref "DY2") (pin "1") (pinfunction "GND_1") (pintype "passive"))
      (node (ref "L4") (pin "1") (pinfunction "1_1") (pintype "passive"))
      (node (ref "Moter1") (pin "6") (pinfunction "GND_6") (pintype "passive"))
      (node (ref "Q1") (pin "1") (pinfunction "E_1") (pintype "passive"))
      (node (ref "R15") (pin "2") (pinfunction "2_2") (pintype "passive"))
      (node (ref "R17") (pin "2") (pinfunction "2_2") (pintype "passive"))
      (node (ref "R29") (pin "2") (pinfunction "2_2") (pintype "passive"))
      (node (ref "R30") (pin "1") (pinfunction "1_1") (pintype "passive"))
      (node (ref "R33") (pin "1") (pinfunction "1_1") (pintype "passive"))
      (node (ref "R34") (pin "2") (pinfunction "2_2") (pintype "passive"))
      (node (ref "R35") (pin "2") (pinfunction "2_2") (pintype "passive"))
      (node (ref "R38") (pin "2") (pinfunction "2_2") (pintype "passive"))
      (node (ref "R48") (pin "2") (pinfunction "2_2") (pintype "passive"))
      (node (ref "R50") (pin "1") (pinfunction "1_1") (pintype "passive"))
      (node (ref "S1") (pin "1") (pinfunction "1_1") (pintype "passive"))
      (node (ref "S1") (pin "2") (pinfunction "2_2") (pintype "passive"))
      (node (ref "S1") (pin "3") (pinfunction "3_3") (pintype "passive"))
      (node (ref "S1") (pin "4") (pinfunction "4_4") (pintype "passive"))
      (node (ref "S10") (pin "1") (pinfunction "1_1") (pintype "passive"))
      (node (ref "S11") (pin "1") (pinfunction "1_1") (pintype "passive"))
      (node (ref "S12") (pin "1") (pinfunction "1_1") (pintype "passive"))
      (node (ref "S2") (pin "1") (pinfunction "1_1") (pintype "passive"))
      (node (ref "S3") (pin "1") (pinfunction "1_1") (pintype "passive"))
      (node (ref "S4") (pin "1") (pinfunction "1_1") (pintype "passive"))
      (node (ref "S5") (pin "1") (pinfunction "1_1") (pintype "passive"))
      (node (ref "S6") (pin "1") (pinfunction "1_1") (pintype "passive"))
      (node (ref "S7") (pin "1") (pinfunction "1_1") (pintype "passive"))
      (node (ref "S9") (pin "1") (pinfunction "1_1") (pintype "passive"))
      (node (ref "U1") (pin "2") (pinfunction "SE_2") (pintype "passive"))
      (node (ref "U1") (pin "4") (pinfunction "GND_4") (pintype "passive"))
      (node (ref "U2") (pin "3") (pinfunction "GND_3") (pintype "passive"))
      (node (ref "U2") (pin "5") (pinfunction "On/Off_5") (pintype "passive"))
      (node (ref "U2") (pin "6") (pinfunction "GND_6") (pintype "passive"))
      (node (ref "U3") (pin "1") (pinfunction "1G_1") (pintype "passive"))
      (node (ref "U3") (pin "10") (pinfunction "10_10") (pintype "passive"))
      (node (ref "U3") (pin "11") (pinfunction "11_11") (pintype "passive"))
      (node (ref "U3") (pin "13") (pinfunction "13_13") (pintype "passive"))
      (node (ref "U3") (pin "15") (pinfunction "15_15") (pintype "passive"))
      (node (ref "U3") (pin "17") (pinfunction "17_17") (pintype "passive"))
      (node (ref "U3") (pin "19") (pinfunction "19_19") (pintype "passive"))
      (node (ref "U3") (pin "3") (pinfunction "3_3") (pintype "passive"))
      (node (ref "U3") (pin "5") (pinfunction "5_5") (pintype "passive"))
      (node (ref "U3") (pin "7") (pinfunction "7_7") (pintype "passive"))
      (node (ref "U3") (pin "9") (pinfunction "9_9") (pintype "passive"))
      (node (ref "blue1") (pin "2") (pinfunction "GND_2") (pintype "passive"))
      (node (ref "oled1") (pin "1") (pinfunction "GND_1") (pintype "passive"))
      (node (ref "oled2") (pin "1") (pinfunction "GND_1") (pintype "passive"))
    )
    (net (code "116") (name "Net-(*2-VBAT)") (class "Default")
      (node (ref "*2") (pin "42") (pinfunction "VBAT_42") (pintype "passive"))
      (node (ref "C18") (pin "2") (pinfunction "2_2") (pintype "passive"))
      (node (ref "R23") (pin "2") (pinfunction "2_2") (pintype "passive"))
    )
    (net (code "117") (name "Net-(*2-VDDA)") (class "Default")
      (node (ref "*2") (pin "31") (pinfunction "VDDA_31") (pintype "passive"))
      (node (ref "R21") (pin "2") (pinfunction "2_2") (pintype "passive"))
    )
    (net (code "118") (name "Net-(*2-VOUT33)") (class "Default")
      (node (ref "*2") (pin "21") (pinfunction "VOUT33_21") (pintype "passive"))
      (node (ref "C10") (pin "2") (pinfunction "2_2") (pintype "passive"))
      (node (ref "C12") (pin "2") (pinfunction "2_2") (pintype "passive"))
      (node (ref "R14") (pin "2") (pinfunction "2_2") (pintype "passive"))
    )
    (net (code "119") (name "Net-(*2-VREFH)") (class "Default")
      (node (ref "*2") (pin "32") (pinfunction "VREFH_32") (pintype "passive"))
      (node (ref "C14") (pin "2") (pinfunction "2_2") (pintype "passive"))
      (node (ref "C15") (pin "2") (pinfunction "2_2") (pintype "passive"))
      (node (ref "C16") (pin "2") (pinfunction "2_2") (pintype "passive"))
      (node (ref "C17") (pin "2") (pinfunction "2_2") (pintype "passive"))
      (node (ref "L3") (pin "2") (pinfunction "2_2") (pintype "passive"))
      (node (ref "R21") (pin "1") (pinfunction "1_1") (pintype "passive"))
    )
    (net (code "120") (name "Net-(*2-VREFL)") (class "Default")
      (node (ref "*2") (pin "33") (pinfunction "VREFL_33") (pintype "passive"))
      (node (ref "C14") (pin "1") (pinfunction "1_1") (pintype "passive"))
      (node (ref "C15") (pin "1") (pinfunction "1_1") (pintype "passive"))
      (node (ref "C16") (pin "1") (pinfunction "1_1") (pintype "passive"))
      (node (ref "C17") (pin "1") (pinfunction "1_1") (pintype "passive"))
      (node (ref "L4") (pin "2") (pinfunction "2_2") (pintype "passive"))
      (node (ref "R26") (pin "1") (pinfunction "1_1") (pintype "passive"))
    )
    (net (code "121") (name "Net-(*2-VREGIN)") (class "Default")
      (node (ref "*2") (pin "22") (pinfunction "VREGIN_22") (pintype "passive"))
      (node (ref "C11") (pin "2") (pinfunction "2_2") (pintype "passive"))
      (node (ref "R18") (pin "2") (pinfunction "2_2") (pintype "passive"))
    )
    (net (code "122") (name "Net-(*2-VSSA)") (class "Default")
      (node (ref "*2") (pin "34") (pinfunction "VSSA_34") (pintype "passive"))
      (node (ref "R26") (pin "2") (pinfunction "2_2") (pintype "passive"))
    )
    (net (code "123") (name "Net-(*3-VDD)") (class "Default")
      (node (ref "*3") (pin "4") (pinfunction "VDD_4") (pintype "passive"))
      (node (ref "C1") (pin "2") (pinfunction "2_2") (pintype "passive"))
      (node (ref "C2") (pin "2") (pinfunction "2_2") (pintype "passive"))
      (node (ref "L1") (pin "2") (pinfunction "2_2") (pintype "passive"))
    )
    (net (code "124") (name "Net-(*9-VBAT)") (class "Default")
      (node (ref "*9") (pin "42") (pinfunction "VBAT_42") (pintype "passive"))
      (node (ref "C57") (pin "2") (pinfunction "2_2") (pintype "passive"))
      (node (ref "R45") (pin "2") (pinfunction "2_2") (pintype "passive"))
    )
    (net (code "125") (name "Net-(*9-VDD-Pad56)") (class "Default")
      (node (ref "*9") (pin "56") (pinfunction "VDD_56") (pintype "passive"))
      (node (ref "C48") (pin "1") (pinfunction "1_1") (pintype "passive"))
    )
    (net (code "126") (name "Net-(*9-VDDA)") (class "Default")
      (node (ref "*9") (pin "31") (pinfunction "VDDA_31") (pintype "passive"))
      (node (ref "R42") (pin "2") (pinfunction "2_2") (pintype "passive"))
    )
    (net (code "127") (name "Net-(*9-VOUT33)") (class "Default")
      (node (ref "*9") (pin "21") (pinfunction "VOUT33_21") (pintype "passive"))
      (node (ref "C49") (pin "2") (pinfunction "2_2") (pintype "passive"))
      (node (ref "C51") (pin "2") (pinfunction "2_2") (pintype "passive"))
      (node (ref "R37") (pin "2") (pinfunction "2_2") (pintype "passive"))
    )
    (net (code "128") (name "Net-(*9-VREFH)") (class "Default")
      (node (ref "*9") (pin "32") (pinfunction "VREFH_32") (pintype "passive"))
      (node (ref "C53") (pin "2") (pinfunction "2_2") (pintype "passive"))
      (node (ref "C54") (pin "2") (pinfunction "2_2") (pintype "passive"))
      (node (ref "C55") (pin "2") (pinfunction "2_2") (pintype "passive"))
      (node (ref "C56") (pin "2") (pinfunction "2_2") (pintype "passive"))
      (node (ref "L7") (pin "2") (pinfunction "2_2") (pintype "passive"))
      (node (ref "R42") (pin "1") (pinfunction "1_1") (pintype "passive"))
    )
    (net (code "129") (name "Net-(*9-VREFL)") (class "Default")
      (node (ref "*9") (pin "33") (pinfunction "VREFL_33") (pintype "passive"))
      (node (ref "C53") (pin "1") (pinfunction "1_1") (pintype "passive"))
      (node (ref "C54") (pin "1") (pinfunction "1_1") (pintype "passive"))
      (node (ref "C55") (pin "1") (pinfunction "1_1") (pintype "passive"))
      (node (ref "C56") (pin "1") (pinfunction "1_1") (pintype "passive"))
      (node (ref "L8") (pin "2") (pinfunction "2_2") (pintype "passive"))
      (node (ref "R46") (pin "1") (pinfunction "1_1") (pintype "passive"))
    )
    (net (code "130") (name "Net-(*9-VREGIN)") (class "Default")
      (node (ref "*9") (pin "22") (pinfunction "VREGIN_22") (pintype "passive"))
      (node (ref "C50") (pin "2") (pinfunction "2_2") (pintype "passive"))
      (node (ref "R39") (pin "2") (pinfunction "2_2") (pintype "passive"))
    )
    (net (code "131") (name "Net-(*9-VSSA)") (class "Default")
      (node (ref "*9") (pin "34") (pinfunction "VSSA_34") (pintype "passive"))
      (node (ref "R46") (pin "2") (pinfunction "2_2") (pintype "passive"))
    )
    (net (code "132") (name "Net-(*10-VDD)") (class "Default")
      (node (ref "*10") (pin "4") (pinfunction "VDD_4") (pintype "passive"))
      (node (ref "C43") (pin "2") (pinfunction "2_2") (pintype "passive"))
      (node (ref "C44") (pin "2") (pinfunction "2_2") (pintype "passive"))
      (node (ref "L6") (pin "2") (pinfunction "2_2") (pintype "passive"))
    )
    (net (code "133") (name "Net-(1-GND)") (class "Default")
      (node (ref "1") (pin "1") (pinfunction "GND_1") (pintype "open_emitter"))
      (node (ref "R27") (pin "1") (pinfunction "1_1") (pintype "passive"))
      (node (ref "R30") (pin "2") (pinfunction "2_2") (pintype "passive"))
    )
    (net (code "134") (name "Net-(D1-A)") (class "Default")
      (node (ref "D1") (pin "1") (pinfunction "A_1") (pintype "passive"))
      (node (ref "L2") (pin "2") (pinfunction "2_2") (pintype "passive"))
      (node (ref "U1") (pin "1") (pinfunction "SC_1") (pintype "passive"))
    )
    (net (code "135") (name "Net-(D2-K)") (class "Default")
      (node (ref "D2") (pin "2") (pinfunction "K_2") (pintype "passive"))
      (node (ref "R15") (pin "1") (pinfunction "1_1") (pintype "passive"))
    )
    (net (code "136") (name "Net-(D3-K)") (class "Default")
      (node (ref "D3") (pin "2") (pinfunction "K_2") (pintype "passive"))
      (node (ref "R19") (pin "1") (pinfunction "1_1") (pintype "passive"))
    )
    (net (code "137") (name "Net-(D4-K)") (class "Default")
      (node (ref "D4") (pin "2") (pinfunction "K_2") (pintype "passive"))
      (node (ref "R20") (pin "1") (pinfunction "1_1") (pintype "passive"))
    )
    (net (code "138") (name "Net-(D5-K)") (class "Default")
      (node (ref "D5") (pin "2") (pinfunction "K_2") (pintype "passive"))
      (node (ref "R22") (pin "1") (pinfunction "1_1") (pintype "passive"))
    )
    (net (code "139") (name "Net-(D6-K)") (class "Default")
      (node (ref "D6") (pin "2") (pinfunction "K_2") (pintype "passive"))
      (node (ref "R24") (pin "1") (pinfunction "1_1") (pintype "passive"))
    )
    (net (code "140") (name "Net-(D7-A)") (class "Default")
      (node (ref "D7") (pin "1") (pinfunction "A_1") (pintype "passive"))
      (node (ref "R25") (pin "1") (pinfunction "1_1") (pintype "passive"))
    )
    (net (code "141") (name "Net-(D8-A)") (class "Default")
      (node (ref "D8") (pin "1") (pinfunction "A_1") (pintype "passive"))
      (node (ref "L5") (pin "1") (pinfunction "1_1") (pintype "passive"))
      (node (ref "U2") (pin "2") (pinfunction "OUT_2") (pintype "passive"))
    )
    (net (code "142") (name "Net-(D9-K)") (class "Default")
      (node (ref "D9") (pin "2") (pinfunction "K_2") (pintype "passive"))
      (node (ref "R34") (pin "1") (pinfunction "1_1") (pintype "passive"))
    )
    (net (code "143") (name "Net-(D10-K)") (class "Default")
      (node (ref "D10") (pin "2") (pinfunction "K_2") (pintype "passive"))
      (node (ref "R35") (pin "1") (pinfunction "1_1") (pintype "passive"))
    )
    (net (code "144") (name "Net-(D11-K)") (class "Default")
      (node (ref "D11") (pin "2") (pinfunction "K_2") (pintype "passive"))
      (node (ref "R38") (pin "1") (pinfunction "1_1") (pintype "passive"))
    )
    (net (code "145") (name "Net-(D12-K)") (class "Default")
      (node (ref "D12") (pin "2") (pinfunction "K_2") (pintype "passive"))
      (node (ref "R40") (pin "1") (pinfunction "1_1") (pintype "passive"))
    )
    (net (code "146") (name "Net-(D13-K)") (class "Default")
      (node (ref "D13") (pin "2") (pinfunction "K_2") (pintype "passive"))
      (node (ref "R41") (pin "1") (pinfunction "1_1") (pintype "passive"))
    )
    (net (code "147") (name "Net-(Q1-B)") (class "Default")
      (node (ref "Q1") (pin "2") (pinfunction "B_2") (pintype "passive"))
      (node (ref "R31") (pin "2") (pinfunction "2_2") (pintype "passive"))
    )
    (net (code "148") (name "Net-(Q1-C)") (class "Default")
      (node (ref "Q1") (pin "3") (pinfunction "C_3") (pintype "passive"))
      (node (ref "bell1") (pin "2") (pinfunction "B_2") (pintype "passive"))
    )
    (net (code "149") (name "Net-(S8-COMMON)") (class "Default")
      (node (ref "CON1") (pin "1") (pinfunction "1_1") (pintype "passive"))
      (node (ref "S8") (pin "1") (pinfunction "COMMON_1") (pintype "passive"))
    )
    (net (code "150") (name "Net-(U1-DRI)") (class "Default")
      (node (ref "R7") (pin "1") (pinfunction "1_1") (pintype "passive"))
      (node (ref "U1") (pin "8") (pinfunction "DRI_8") (pintype "passive"))
    )
    (net (code "151") (name "Net-(U1-FB)") (class "Default")
      (node (ref "R16") (pin "1") (pinfunction "1_1") (pintype "passive"))
      (node (ref "R17") (pin "1") (pinfunction "1_1") (pintype "passive"))
      (node (ref "U1") (pin "5") (pinfunction "FB_5") (pintype "passive"))
    )
    (net (code "152") (name "Net-(U1-IPK)") (class "Default")
      (node (ref "L2") (pin "1") (pinfunction "1_1") (pintype "passive"))
      (node (ref "R6") (pin "1") (pinfunction "1_1") (pintype "passive"))
      (node (ref "R7") (pin "2") (pinfunction "2_2") (pintype "passive"))
      (node (ref "U1") (pin "7") (pinfunction "IPK_7") (pintype "passive"))
    )
    (net (code "153") (name "Net-(U1-TC)") (class "Default")
      (node (ref "C8") (pin "1") (pinfunction "1_1") (pintype "passive"))
      (node (ref "U1") (pin "3") (pinfunction "TC_3") (pintype "passive"))
    )
    (net (code "154") (name "unconnected-(*1-Pad12)") (class "Default")
      (node (ref "*1") (pin "12") (pinfunction "12_12") (pintype "passive"))
    )
    (net (code "155") (name "unconnected-(*1-Pad13)") (class "Default")
      (node (ref "*1") (pin "13") (pinfunction "13_13") (pintype "passive"))
    )
    (net (code "156") (name "unconnected-(*1-Pad14)") (class "Default")
      (node (ref "*1") (pin "14") (pinfunction "14_14") (pintype "passive"))
    )
    (net (code "157") (name "unconnected-(*1-Pad16)") (class "Default")
      (node (ref "*1") (pin "16") (pinfunction "16_16") (pintype "passive"))
    )
    (net (code "158") (name "unconnected-(*1-Pad18)") (class "Default")
      (node (ref "*1") (pin "18") (pinfunction "18_18") (pintype "passive"))
    )
    (net (code "159") (name "unconnected-(*1-Pad19)") (class "Default")
      (node (ref "*1") (pin "19") (pinfunction "19_19") (pintype "passive"))
    )
    (net (code "160") (name "unconnected-(*2-ADC0_DM1-Pad24)") (class "Default")
      (node (ref "*2") (pin "24") (pinfunction "ADC0_DM1_24") (pintype "passive"))
    )
    (net (code "161") (name "unconnected-(*2-ADC0_DP1-Pad23)") (class "Default")
      (node (ref "*2") (pin "23") (pinfunction "ADC0_DP1_23") (pintype "passive"))
    )
    (net (code "162") (name "unconnected-(*2-ADC0_SE16-Pad36)") (class "Default")
      (node (ref "*2") (pin "36") (pinfunction "ADC0_SE16_36") (pintype "passive"))
    )
    (net (code "163") (name "unconnected-(*2-ADC1_DM1-Pad26)") (class "Default")
      (node (ref "*2") (pin "26") (pinfunction "ADC1_DM1_26") (pintype "passive"))
    )
    (net (code "164") (name "unconnected-(*2-ADC1_DP1-Pad25)") (class "Default")
      (node (ref "*2") (pin "25") (pinfunction "ADC1_DP1_25") (pintype "passive"))
    )
    (net (code "165") (name "unconnected-(*2-ADC1_SE16-Pad35)") (class "Default")
      (node (ref "*2") (pin "35") (pinfunction "ADC1_SE16_35") (pintype "passive"))
    )
    (net (code "166") (name "unconnected-(*2-ADC1_SE18-Pad37)") (class "Default")
      (node (ref "*2") (pin "37") (pinfunction "ADC1_SE18_37") (pintype "passive"))
    )
    (net (code "167") (name "unconnected-(*2-DAC0{slash}ADC0_SE23-Pad38)") (class "Default")
      (node (ref "*2") (pin "38") (pinfunction "DAC0/ADC0_SE23_38") (pintype "passive"))
    )
    (net (code "168") (name "unconnected-(*2-DAC1{slash}ADC1_SE23-Pad39)") (class "Default")
      (node (ref "*2") (pin "39") (pinfunction "DAC1/ADC1_SE23_39") (pintype "passive"))
    )
    (net (code "169") (name "unconnected-(*2-PGA0_DM{slash}ADC0_DM0{slash}ADC1_DM3-Pad28)") (class "Default")
      (node (ref "*2") (pin "28") (pinfunction "PGA0_DM/ADC0_DM0/ADC1_DM3_28") (pintype "passive"))
    )
    (net (code "170") (name "unconnected-(*2-PGA0_DP{slash}ADC0_DP0{slash}ADC1_DP3-Pad27)") (class "Default")
      (node (ref "*2") (pin "27") (pinfunction "PGA0_DP/ADC0_DP0/ADC1_DP3_27") (pintype "passive"))
    )
    (net (code "171") (name "unconnected-(*2-PGA1_DM{slash}ADC1_DM0{slash}ADC0_DM3-Pad30)") (class "Default")
      (node (ref "*2") (pin "30") (pinfunction "PGA1_DM/ADC1_DM0/ADC0_DM3_30") (pintype "passive"))
    )
    (net (code "172") (name "unconnected-(*2-PGA1_DP{slash}ADC1_DP0{slash}ADC0_DP3-Pad29)") (class "Default")
      (node (ref "*2") (pin "29") (pinfunction "PGA1_DP/ADC1_DP0/ADC0_DP3_29") (pintype "passive"))
    )
    (net (code "173") (name "unconnected-(*2-PTA5-Pad55)") (class "Default")
      (node (ref "*2") (pin "55") (pinfunction "PTA5_55") (pintype "passive"))
    )
    (net (code "174") (name "unconnected-(*2-PTA6-Pad58)") (class "Default")
      (node (ref "*2") (pin "58") (pinfunction "PTA6_58") (pintype "passive"))
    )
    (net (code "175") (name "unconnected-(*2-PTA9-Pad61)") (class "Default")
      (node (ref "*2") (pin "61") (pinfunction "PTA9_61") (pintype "passive"))
    )
    (net (code "176") (name "unconnected-(*2-PTA28-Pad79)") (class "Default")
      (node (ref "*2") (pin "79") (pinfunction "PTA28_79") (pintype "passive"))
    )
    (net (code "177") (name "unconnected-(*2-PTB8-Pad89)") (class "Default")
      (node (ref "*2") (pin "89") (pinfunction "PTB8_89") (pintype "passive"))
    )
    (net (code "178") (name "unconnected-(*2-PTB9-Pad90)") (class "Default")
      (node (ref "*2") (pin "90") (pinfunction "PTB9_90") (pintype "passive"))
    )
    (net (code "179") (name "unconnected-(*2-PTB20-Pad99)") (class "Default")
      (node (ref "*2") (pin "99") (pinfunction "PTB20_99") (pintype "passive"))
    )
    (net (code "180") (name "unconnected-(*2-PTB23-Pad102)") (class "Default")
      (node (ref "*2") (pin "102") (pinfunction "PTB23_102") (pintype "passive"))
    )
    (net (code "181") (name "unconnected-(*2-PTC3-Pad106)") (class "Default")
      (node (ref "*2") (pin "106") (pinfunction "PTC3_106") (pintype "passive"))
    )
    (net (code "182") (name "unconnected-(*2-PTC10-Pad115)") (class "Default")
      (node (ref "*2") (pin "115") (pinfunction "PTC10_115") (pintype "passive"))
    )
    (net (code "183") (name "unconnected-(*2-PTC13-Pad118)") (class "Default")
      (node (ref "*2") (pin "118") (pinfunction "PTC13_118") (pintype "passive"))
    )
    (net (code "184") (name "unconnected-(*2-PTC14-Pad119)") (class "Default")
      (node (ref "*2") (pin "119") (pinfunction "PTC14_119") (pintype "passive"))
    )
    (net (code "185") (name "unconnected-(*2-PTC15-Pad120)") (class "Default")
      (node (ref "*2") (pin "120") (pinfunction "PTC15_120") (pintype "passive"))
    )
    (net (code "186") (name "unconnected-(*2-PTC16-Pad123)") (class "Default")
      (node (ref "*2") (pin "123") (pinfunction "PTC16_123") (pintype "passive"))
    )
    (net (code "187") (name "unconnected-(*2-PTC17-Pad124)") (class "Default")
      (node (ref "*2") (pin "124") (pinfunction "PTC17_124") (pintype "passive"))
    )
    (net (code "188") (name "unconnected-(*2-PTC18-Pad125)") (class "Default")
      (node (ref "*2") (pin "125") (pinfunction "PTC18_125") (pintype "passive"))
    )
    (net (code "189") (name "unconnected-(*2-PTC19-Pad126)") (class "Default")
      (node (ref "*2") (pin "126") (pinfunction "PTC19_126") (pintype "passive"))
    )
    (net (code "190") (name "unconnected-(*2-PTD0-Pad127)") (class "Default")
      (node (ref "*2") (pin "127") (pinfunction "PTD0_127") (pintype "passive"))
    )
    (net (code "191") (name "unconnected-(*2-PTD3-Pad130)") (class "Default")
      (node (ref "*2") (pin "130") (pinfunction "PTD3_130") (pintype "passive"))
    )
    (net (code "192") (name "unconnected-(*2-PTD4-Pad131)") (class "Default")
      (node (ref "*2") (pin "131") (pinfunction "PTD4_131") (pintype "passive"))
    )
    (net (code "193") (name "unconnected-(*2-PTD5-Pad132)") (class "Default")
      (node (ref "*2") (pin "132") (pinfunction "PTD5_132") (pintype "passive"))
    )
    (net (code "194") (name "unconnected-(*2-PTD6-Pad133)") (class "Default")
      (node (ref "*2") (pin "133") (pinfunction "PTD6_133") (pintype "passive"))
    )
    (net (code "195") (name "unconnected-(*2-PTE3-Pad4)") (class "Default")
      (node (ref "*2") (pin "4") (pinfunction "PTE3_4") (pintype "passive"))
    )
    (net (code "196") (name "unconnected-(*2-PTE4-Pad7)") (class "Default")
      (node (ref "*2") (pin "7") (pinfunction "PTE4_7") (pintype "passive"))
    )
    (net (code "197") (name "unconnected-(*2-PTE11-Pad14)") (class "Default")
      (node (ref "*2") (pin "14") (pinfunction "PTE11_14") (pintype "passive"))
    )
    (net (code "198") (name "unconnected-(*2-PTE12-Pad15)") (class "Default")
      (node (ref "*2") (pin "15") (pinfunction "PTE12_15") (pintype "passive"))
    )
    (net (code "199") (name "unconnected-(*2-PTE26-Pad47)") (class "Default")
      (node (ref "*2") (pin "47") (pinfunction "PTE26_47") (pintype "passive"))
    )
    (net (code "200") (name "unconnected-(*2-PTE27-Pad48)") (class "Default")
      (node (ref "*2") (pin "48") (pinfunction "PTE27_48") (pintype "passive"))
    )
    (net (code "201") (name "unconnected-(*2-PTE28-Pad49)") (class "Default")
      (node (ref "*2") (pin "49") (pinfunction "PTE28_49") (pintype "passive"))
    )
    (net (code "202") (name "unconnected-(*2-USB0_DM-Pad20)") (class "Default")
      (node (ref "*2") (pin "20") (pinfunction "USB0_DM_20") (pintype "passive"))
    )
    (net (code "203") (name "unconnected-(*2-USB0_DP-Pad19)") (class "Default")
      (node (ref "*2") (pin "19") (pinfunction "USB0_DP_19") (pintype "passive"))
    )
    (net (code "204") (name "unconnected-(*3-OE-Pad1)") (class "Default")
      (node (ref "*3") (pin "1") (pinfunction "OE_1") (pintype "passive"))
    )
    (net (code "205") (name "unconnected-(*4-Pad1)") (class "Default")
      (node (ref "*4") (pin "1") (pinfunction "1_1") (pintype "passive"))
    )
    (net (code "206") (name "unconnected-(*4-Pad4)") (class "Default")
      (node (ref "*4") (pin "4") (pinfunction "4_4") (pintype "passive"))
    )
    (net (code "207") (name "unconnected-(*9-ADC0_DM1-Pad24)") (class "Default")
      (node (ref "*9") (pin "24") (pinfunction "ADC0_DM1_24") (pintype "passive"))
    )
    (net (code "208") (name "unconnected-(*9-ADC0_DP1-Pad23)") (class "Default")
      (node (ref "*9") (pin "23") (pinfunction "ADC0_DP1_23") (pintype "passive"))
    )
    (net (code "209") (name "unconnected-(*9-ADC0_SE16-Pad36)") (class "Default")
      (node (ref "*9") (pin "36") (pinfunction "ADC0_SE16_36") (pintype "passive"))
    )
    (net (code "210") (name "unconnected-(*9-ADC1_DM1-Pad26)") (class "Default")
      (node (ref "*9") (pin "26") (pinfunction "ADC1_DM1_26") (pintype "passive"))
    )
    (net (code "211") (name "unconnected-(*9-ADC1_DP1-Pad25)") (class "Default")
      (node (ref "*9") (pin "25") (pinfunction "ADC1_DP1_25") (pintype "passive"))
    )
    (net (code "212") (name "unconnected-(*9-ADC1_SE16-Pad35)") (class "Default")
      (node (ref "*9") (pin "35") (pinfunction "ADC1_SE16_35") (pintype "passive"))
    )
    (net (code "213") (name "unconnected-(*9-ADC1_SE18-Pad37)") (class "Default")
      (node (ref "*9") (pin "37") (pinfunction "ADC1_SE18_37") (pintype "passive"))
    )
    (net (code "214") (name "unconnected-(*9-DAC0{slash}ADC0_SE23-Pad38)") (class "Default")
      (node (ref "*9") (pin "38") (pinfunction "DAC0/ADC0_SE23_38") (pintype "passive"))
    )
    (net (code "215") (name "unconnected-(*9-DAC1{slash}ADC1_SE23-Pad39)") (class "Default")
      (node (ref "*9") (pin "39") (pinfunction "DAC1/ADC1_SE23_39") (pintype "passive"))
    )
    (net (code "216") (name "unconnected-(*9-PGA0_DM{slash}ADC0_DM0{slash}ADC1_DM3-Pad28)") (class "Default")
      (node (ref "*9") (pin "28") (pinfunction "PGA0_DM/ADC0_DM0/ADC1_DM3_28") (pintype "passive"))
    )
    (net (code "217") (name "unconnected-(*9-PGA0_DP{slash}ADC0_DP0{slash}ADC1_DP3-Pad27)") (class "Default")
      (node (ref "*9") (pin "27") (pinfunction "PGA0_DP/ADC0_DP0/ADC1_DP3_27") (pintype "passive"))
    )
    (net (code "218") (name "unconnected-(*9-PGA1_DM{slash}ADC1_DM0{slash}ADC0_DM3-Pad30)") (class "Default")
      (node (ref "*9") (pin "30") (pinfunction "PGA1_DM/ADC1_DM0/ADC0_DM3_30") (pintype "passive"))
    )
    (net (code "219") (name "unconnected-(*9-PGA1_DP{slash}ADC1_DP0{slash}ADC0_DP3-Pad29)") (class "Default")
      (node (ref "*9") (pin "29") (pinfunction "PGA1_DP/ADC1_DP0/ADC0_DP3_29") (pintype "passive"))
    )
    (net (code "220") (name "unconnected-(*9-PTA5-Pad55)") (class "Default")
      (node (ref "*9") (pin "55") (pinfunction "PTA5_55") (pintype "passive"))
    )
    (net (code "221") (name "unconnected-(*9-PTA6-Pad58)") (class "Default")
      (node (ref "*9") (pin "58") (pinfunction "PTA6_58") (pintype "passive"))
    )
    (net (code "222") (name "unconnected-(*9-PTA7-Pad59)") (class "Default")
      (node (ref "*9") (pin "59") (pinfunction "PTA7_59") (pintype "passive"))
    )
    (net (code "223") (name "unconnected-(*9-PTA8-Pad60)") (class "Default")
      (node (ref "*9") (pin "60") (pinfunction "PTA8_60") (pintype "passive"))
    )
    (net (code "224") (name "unconnected-(*9-PTA9-Pad61)") (class "Default")
      (node (ref "*9") (pin "61") (pinfunction "PTA9_61") (pintype "passive"))
    )
    (net (code "225") (name "unconnected-(*9-PTA10-Pad62)") (class "Default")
      (node (ref "*9") (pin "62") (pinfunction "PTA10_62") (pintype "passive"))
    )
    (net (code "226") (name "unconnected-(*9-PTA11-Pad63)") (class "Default")
      (node (ref "*9") (pin "63") (pinfunction "PTA11_63") (pintype "passive"))
    )
    (net (code "227") (name "unconnected-(*9-PTA12-Pad64)") (class "Default")
      (node (ref "*9") (pin "64") (pinfunction "PTA12_64") (pintype "passive"))
    )
    (net (code "228") (name "unconnected-(*9-PTA13-Pad65)") (class "Default")
      (node (ref "*9") (pin "65") (pinfunction "PTA13_65") (pintype "passive"))
    )
    (net (code "229") (name "unconnected-(*9-PTA14-Pad66)") (class "Default")
      (node (ref "*9") (pin "66") (pinfunction "PTA14_66") (pintype "passive"))
    )
    (net (code "230") (name "unconnected-(*9-PTA15-Pad67)") (class "Default")
      (node (ref "*9") (pin "67") (pinfunction "PTA15_67") (pintype "passive"))
    )
    (net (code "231") (name "unconnected-(*9-PTA16-Pad68)") (class "Default")
      (node (ref "*9") (pin "68") (pinfunction "PTA16_68") (pintype "passive"))
    )
    (net (code "232") (name "unconnected-(*9-PTA17-Pad69)") (class "Default")
      (node (ref "*9") (pin "69") (pinfunction "PTA17_69") (pintype "passive"))
    )
    (net (code "233") (name "unconnected-(*9-PTA28-Pad79)") (class "Default")
      (node (ref "*9") (pin "79") (pinfunction "PTA28_79") (pintype "passive"))
    )
    (net (code "234") (name "unconnected-(*9-PTB8-Pad89)") (class "Default")
      (node (ref "*9") (pin "89") (pinfunction "PTB8_89") (pintype "passive"))
    )
    (net (code "235") (name "unconnected-(*9-PTB9-Pad90)") (class "Default")
      (node (ref "*9") (pin "90") (pinfunction "PTB9_90") (pintype "passive"))
    )
    (net (code "236") (name "unconnected-(*9-PTB10-Pad91)") (class "Default")
      (node (ref "*9") (pin "91") (pinfunction "PTB10_91") (pintype "passive"))
    )
    (net (code "237") (name "unconnected-(*9-PTB11-Pad92)") (class "Default")
      (node (ref "*9") (pin "92") (pinfunction "PTB11_92") (pintype "passive"))
    )
    (net (code "238") (name "unconnected-(*9-PTB16-Pad95)") (class "Default")
      (node (ref "*9") (pin "95") (pinfunction "PTB16_95") (pintype "passive"))
    )
    (net (code "239") (name "unconnected-(*9-PTB17-Pad96)") (class "Default")
      (node (ref "*9") (pin "96") (pinfunction "PTB17_96") (pintype "passive"))
    )
    (net (code "240") (name "unconnected-(*9-PTB18-Pad97)") (class "Default")
      (node (ref "*9") (pin "97") (pinfunction "PTB18_97") (pintype "passive"))
    )
    (net (code "241") (name "unconnected-(*9-PTB19-Pad98)") (class "Default")
      (node (ref "*9") (pin "98") (pinfunction "PTB19_98") (pintype "passive"))
    )
    (net (code "242") (name "unconnected-(*9-PTB20-Pad99)") (class "Default")
      (node (ref "*9") (pin "99") (pinfunction "PTB20_99") (pintype "passive"))
    )
    (net (code "243") (name "unconnected-(*9-PTB23-Pad102)") (class "Default")
      (node (ref "*9") (pin "102") (pinfunction "PTB23_102") (pintype "passive"))
    )
    (net (code "244") (name "unconnected-(*9-PTC0-Pad103)") (class "Default")
      (node (ref "*9") (pin "103") (pinfunction "PTC0_103") (pintype "passive"))
    )
    (net (code "245") (name "unconnected-(*9-PTC1-Pad104)") (class "Default")
      (node (ref "*9") (pin "104") (pinfunction "PTC1_104") (pintype "passive"))
    )
    (net (code "246") (name "unconnected-(*9-PTC2-Pad105)") (class "Default")
      (node (ref "*9") (pin "105") (pinfunction "PTC2_105") (pintype "passive"))
    )
    (net (code "247") (name "unconnected-(*9-PTC3-Pad106)") (class "Default")
      (node (ref "*9") (pin "106") (pinfunction "PTC3_106") (pintype "passive"))
    )
    (net (code "248") (name "unconnected-(*9-PTC4-Pad109)") (class "Default")
      (node (ref "*9") (pin "109") (pinfunction "PTC4_109") (pintype "passive"))
    )
    (net (code "249") (name "unconnected-(*9-PTC5-Pad110)") (class "Default")
      (node (ref "*9") (pin "110") (pinfunction "PTC5_110") (pintype "passive"))
    )
    (net (code "250") (name "unconnected-(*9-PTC6-Pad111)") (class "Default")
      (node (ref "*9") (pin "111") (pinfunction "PTC6_111") (pintype "passive"))
    )
    (net (code "251") (name "unconnected-(*9-PTC7-Pad112)") (class "Default")
      (node (ref "*9") (pin "112") (pinfunction "PTC7_112") (pintype "passive"))
    )
    (net (code "252") (name "unconnected-(*9-PTC8-Pad113)") (class "Default")
      (node (ref "*9") (pin "113") (pinfunction "PTC8_113") (pintype "passive"))
    )
    (net (code "253") (name "unconnected-(*9-PTC9-Pad114)") (class "Default")
      (node (ref "*9") (pin "114") (pinfunction "PTC9_114") (pintype "passive"))
    )
    (net (code "254") (name "unconnected-(*9-PTC10-Pad115)") (class "Default")
      (node (ref "*9") (pin "115") (pinfunction "PTC10_115") (pintype "passive"))
    )
    (net (code "255") (name "unconnected-(*9-PTC11-Pad116)") (class "Default")
      (node (ref "*9") (pin "116") (pinfunction "PTC11_116") (pintype "passive"))
    )
    (net (code "256") (name "unconnected-(*9-PTC12-Pad117)") (class "Default")
      (node (ref "*9") (pin "117") (pinfunction "PTC12_117") (pintype "passive"))
    )
    (net (code "257") (name "unconnected-(*9-PTC13-Pad118)") (class "Default")
      (node (ref "*9") (pin "118") (pinfunction "PTC13_118") (pintype "passive"))
    )
    (net (code "258") (name "unconnected-(*9-PTC14-Pad119)") (class "Default")
      (node (ref "*9") (pin "119") (pinfunction "PTC14_119") (pintype "passive"))
    )
    (net (code "259") (name "unconnected-(*9-PTC15-Pad120)") (class "Default")
      (node (ref "*9") (pin "120") (pinfunction "PTC15_120") (pintype "passive"))
    )
    (net (code "260") (name "unconnected-(*9-PTC16-Pad123)") (class "Default")
      (node (ref "*9") (pin "123") (pinfunction "PTC16_123") (pintype "passive"))
    )
    (net (code "261") (name "unconnected-(*9-PTC17-Pad124)") (class "Default")
      (node (ref "*9") (pin "124") (pinfunction "PTC17_124") (pintype "passive"))
    )
    (net (code "262") (name "unconnected-(*9-PTC18-Pad125)") (class "Default")
      (node (ref "*9") (pin "125") (pinfunction "PTC18_125") (pintype "passive"))
    )
    (net (code "263") (name "unconnected-(*9-PTC19-Pad126)") (class "Default")
      (node (ref "*9") (pin "126") (pinfunction "PTC19_126") (pintype "passive"))
    )
    (net (code "264") (name "unconnected-(*9-PTD0-Pad127)") (class "Default")
      (node (ref "*9") (pin "127") (pinfunction "PTD0_127") (pintype "passive"))
    )
    (net (code "265") (name "unconnected-(*9-PTD1-Pad128)") (class "Default")
      (node (ref "*9") (pin "128") (pinfunction "PTD1_128") (pintype "passive"))
    )
    (net (code "266") (name "unconnected-(*9-PTD2-Pad129)") (class "Default")
      (node (ref "*9") (pin "129") (pinfunction "PTD2_129") (pintype "passive"))
    )
    (net (code "267") (name "unconnected-(*9-PTD3-Pad130)") (class "Default")
      (node (ref "*9") (pin "130") (pinfunction "PTD3_130") (pintype "passive"))
    )
    (net (code "268") (name "unconnected-(*9-PTD4-Pad131)") (class "Default")
      (node (ref "*9") (pin "131") (pinfunction "PTD4_131") (pintype "passive"))
    )
    (net (code "269") (name "unconnected-(*9-PTD5-Pad132)") (class "Default")
      (node (ref "*9") (pin "132") (pinfunction "PTD5_132") (pintype "passive"))
    )
    (net (code "270") (name "unconnected-(*9-PTD6-Pad133)") (class "Default")
      (node (ref "*9") (pin "133") (pinfunction "PTD6_133") (pintype "passive"))
    )
    (net (code "271") (name "unconnected-(*9-PTD7-Pad136)") (class "Default")
      (node (ref "*9") (pin "136") (pinfunction "PTD7_136") (pintype "passive"))
    )
    (net (code "272") (name "unconnected-(*9-PTD8-Pad137)") (class "Default")
      (node (ref "*9") (pin "137") (pinfunction "PTD8_137") (pintype "passive"))
    )
    (net (code "273") (name "unconnected-(*9-PTD9-Pad138)") (class "Default")
      (node (ref "*9") (pin "138") (pinfunction "PTD9_138") (pintype "passive"))
    )
    (net (code "274") (name "unconnected-(*9-PTD10-Pad139)") (class "Default")
      (node (ref "*9") (pin "139") (pinfunction "PTD10_139") (pintype "passive"))
    )
    (net (code "275") (name "unconnected-(*9-PTD11-Pad140)") (class "Default")
      (node (ref "*9") (pin "140") (pinfunction "PTD11_140") (pintype "passive"))
    )
    (net (code "276") (name "unconnected-(*9-PTD12-Pad141)") (class "Default")
      (node (ref "*9") (pin "141") (pinfunction "PTD12_141") (pintype "passive"))
    )
    (net (code "277") (name "unconnected-(*9-PTD13-Pad142)") (class "Default")
      (node (ref "*9") (pin "142") (pinfunction "PTD13_142") (pintype "passive"))
    )
    (net (code "278") (name "unconnected-(*9-PTE0-Pad1)") (class "Default")
      (node (ref "*9") (pin "1") (pinfunction "PTE0_1") (pintype "passive"))
    )
    (net (code "279") (name "unconnected-(*9-PTE1-Pad2)") (class "Default")
      (node (ref "*9") (pin "2") (pinfunction "PTE1_2") (pintype "passive"))
    )
    (net (code "280") (name "unconnected-(*9-PTE2-Pad3)") (class "Default")
      (node (ref "*9") (pin "3") (pinfunction "PTE2_3") (pintype "passive"))
    )
    (net (code "281") (name "unconnected-(*9-PTE3-Pad4)") (class "Default")
      (node (ref "*9") (pin "4") (pinfunction "PTE3_4") (pintype "passive"))
    )
    (net (code "282") (name "unconnected-(*9-PTE4-Pad7)") (class "Default")
      (node (ref "*9") (pin "7") (pinfunction "PTE4_7") (pintype "passive"))
    )
    (net (code "283") (name "unconnected-(*9-PTE5-Pad8)") (class "Default")
      (node (ref "*9") (pin "8") (pinfunction "PTE5_8") (pintype "passive"))
    )
    (net (code "284") (name "unconnected-(*9-PTE6-Pad9)") (class "Default")
      (node (ref "*9") (pin "9") (pinfunction "PTE6_9") (pintype "passive"))
    )
    (net (code "285") (name "unconnected-(*9-PTE7-Pad10)") (class "Default")
      (node (ref "*9") (pin "10") (pinfunction "PTE7_10") (pintype "passive"))
    )
    (net (code "286") (name "unconnected-(*9-PTE8-Pad11)") (class "Default")
      (node (ref "*9") (pin "11") (pinfunction "PTE8_11") (pintype "passive"))
    )
    (net (code "287") (name "unconnected-(*9-PTE9-Pad12)") (class "Default")
      (node (ref "*9") (pin "12") (pinfunction "PTE9_12") (pintype "passive"))
    )
    (net (code "288") (name "unconnected-(*9-PTE10-Pad13)") (class "Default")
      (node (ref "*9") (pin "13") (pinfunction "PTE10_13") (pintype "passive"))
    )
    (net (code "289") (name "unconnected-(*9-PTE11-Pad14)") (class "Default")
      (node (ref "*9") (pin "14") (pinfunction "PTE11_14") (pintype "passive"))
    )
    (net (code "290") (name "unconnected-(*9-PTE12-Pad15)") (class "Default")
      (node (ref "*9") (pin "15") (pinfunction "PTE12_15") (pintype "passive"))
    )
    (net (code "291") (name "unconnected-(*9-PTE24-Pad45)") (class "Default")
      (node (ref "*9") (pin "45") (pinfunction "PTE24_45") (pintype "passive"))
    )
    (net (code "292") (name "unconnected-(*9-PTE25-Pad46)") (class "Default")
      (node (ref "*9") (pin "46") (pinfunction "PTE25_46") (pintype "passive"))
    )
    (net (code "293") (name "unconnected-(*9-PTE28-Pad49)") (class "Default")
      (node (ref "*9") (pin "49") (pinfunction "PTE28_49") (pintype "passive"))
    )
    (net (code "294") (name "unconnected-(*9-USB0_DM-Pad20)") (class "Default")
      (node (ref "*9") (pin "20") (pinfunction "USB0_DM_20") (pintype "passive"))
    )
    (net (code "295") (name "unconnected-(*9-USB0_DP-Pad19)") (class "Default")
      (node (ref "*9") (pin "19") (pinfunction "USB0_DP_19") (pintype "passive"))
    )
    (net (code "296") (name "unconnected-(*10-OE-Pad1)") (class "Default")
      (node (ref "*10") (pin "1") (pinfunction "OE_1") (pintype "passive"))
    )
    (net (code "297") (name "unconnected-(*11-Pad1)") (class "Default")
      (node (ref "*11") (pin "1") (pinfunction "1_1") (pintype "passive"))
    )
    (net (code "298") (name "unconnected-(*11-Pad4)") (class "Default")
      (node (ref "*11") (pin "4") (pinfunction "4_4") (pintype "passive"))
    )
    (net (code "299") (name "unconnected-(*12-Pad12)") (class "Default")
      (node (ref "*12") (pin "12") (pinfunction "12_12") (pintype "passive"))
    )
    (net (code "300") (name "unconnected-(*12-Pad13)") (class "Default")
      (node (ref "*12") (pin "13") (pinfunction "13_13") (pintype "passive"))
    )
    (net (code "301") (name "unconnected-(*12-Pad14)") (class "Default")
      (node (ref "*12") (pin "14") (pinfunction "14_14") (pintype "passive"))
    )
    (net (code "302") (name "unconnected-(*12-Pad16)") (class "Default")
      (node (ref "*12") (pin "16") (pinfunction "16_16") (pintype "passive"))
    )
    (net (code "303") (name "unconnected-(*12-Pad18)") (class "Default")
      (node (ref "*12") (pin "18") (pinfunction "18_18") (pintype "passive"))
    )
    (net (code "304") (name "unconnected-(*12-Pad19)") (class "Default")
      (node (ref "*12") (pin "19") (pinfunction "19_19") (pintype "passive"))
    )
    (net (code "305") (name "unconnected-(BMQ1-Pad5)") (class "Default")
      (node (ref "BMQ1") (pin "5") (pinfunction "5_5") (pintype "passive"))
    )
    (net (code "306") (name "unconnected-(BMQ1-Pad6)") (class "Default")
      (node (ref "BMQ1") (pin "6") (pinfunction "6_6") (pintype "passive"))
    )
    (net (code "307") (name "unconnected-(BMQ2-Pad5)") (class "Default")
      (node (ref "BMQ2") (pin "5") (pinfunction "5_5") (pintype "passive"))
    )
    (net (code "308") (name "unconnected-(BMQ2-Pad6)") (class "Default")
      (node (ref "BMQ2") (pin "6") (pinfunction "6_6") (pintype "passive"))
    )
  )
)
